# touch_glove.net
KiCad netlist of a schematic drawn in EAGLE
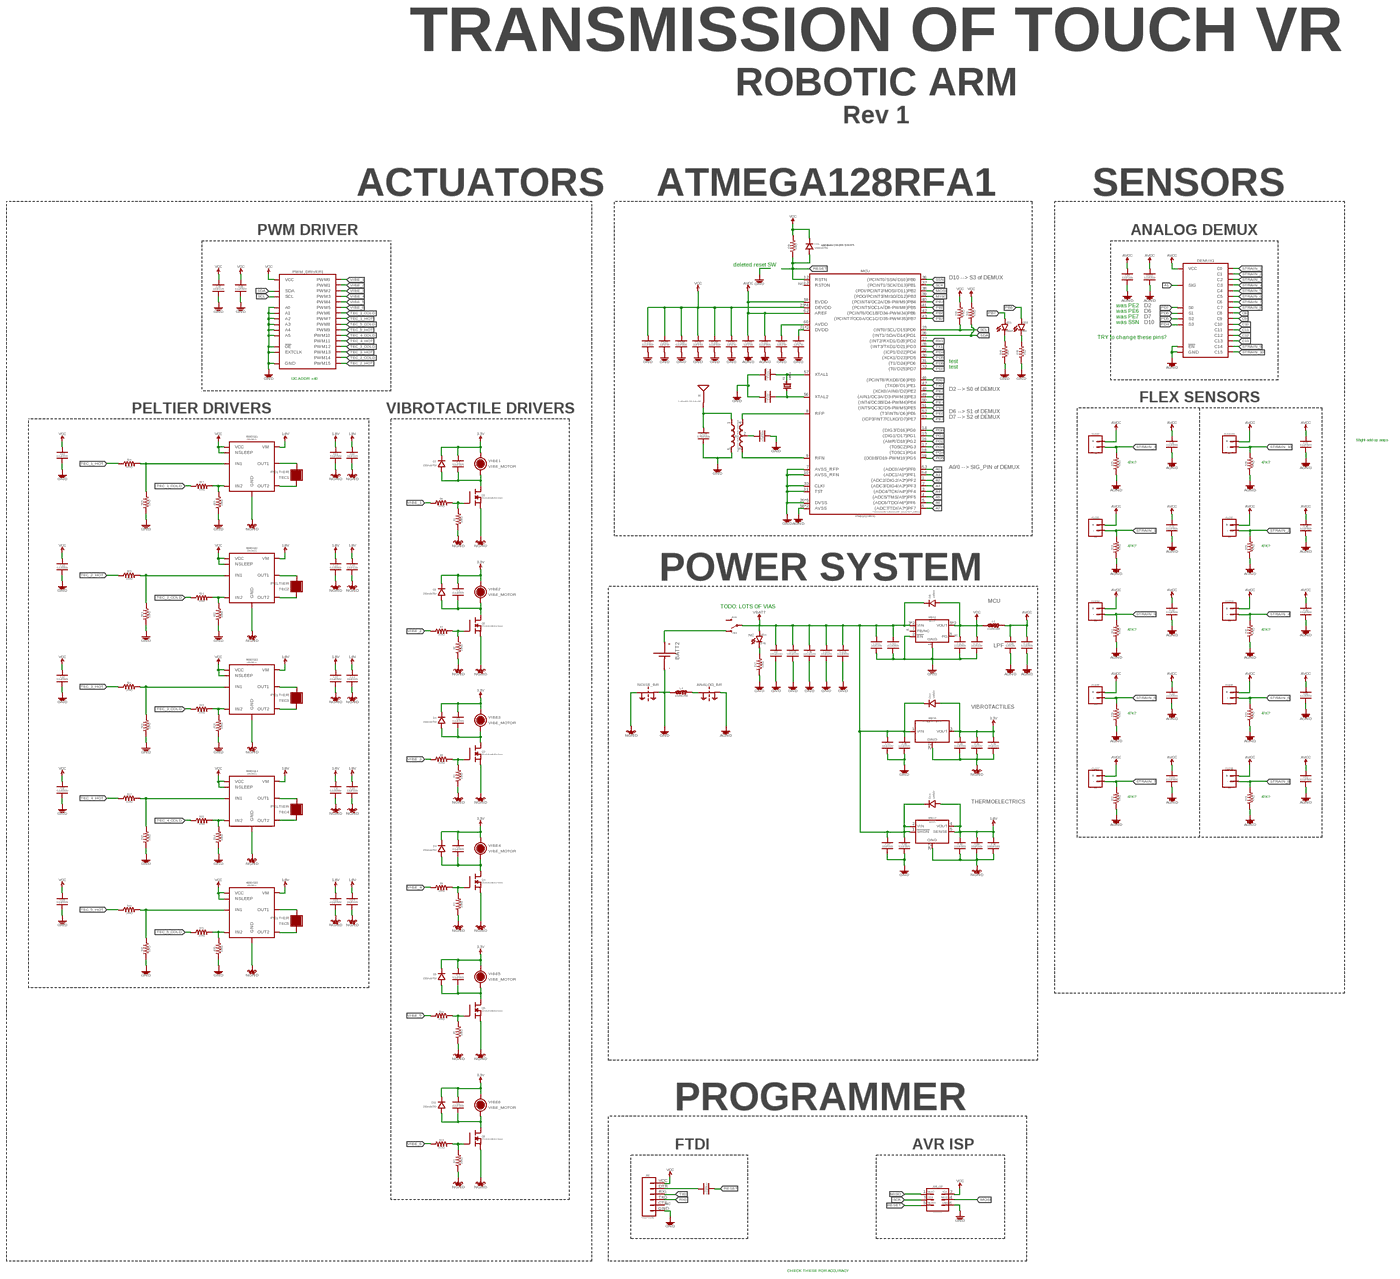
[diagram p0: schematic, sheet 1, overview]
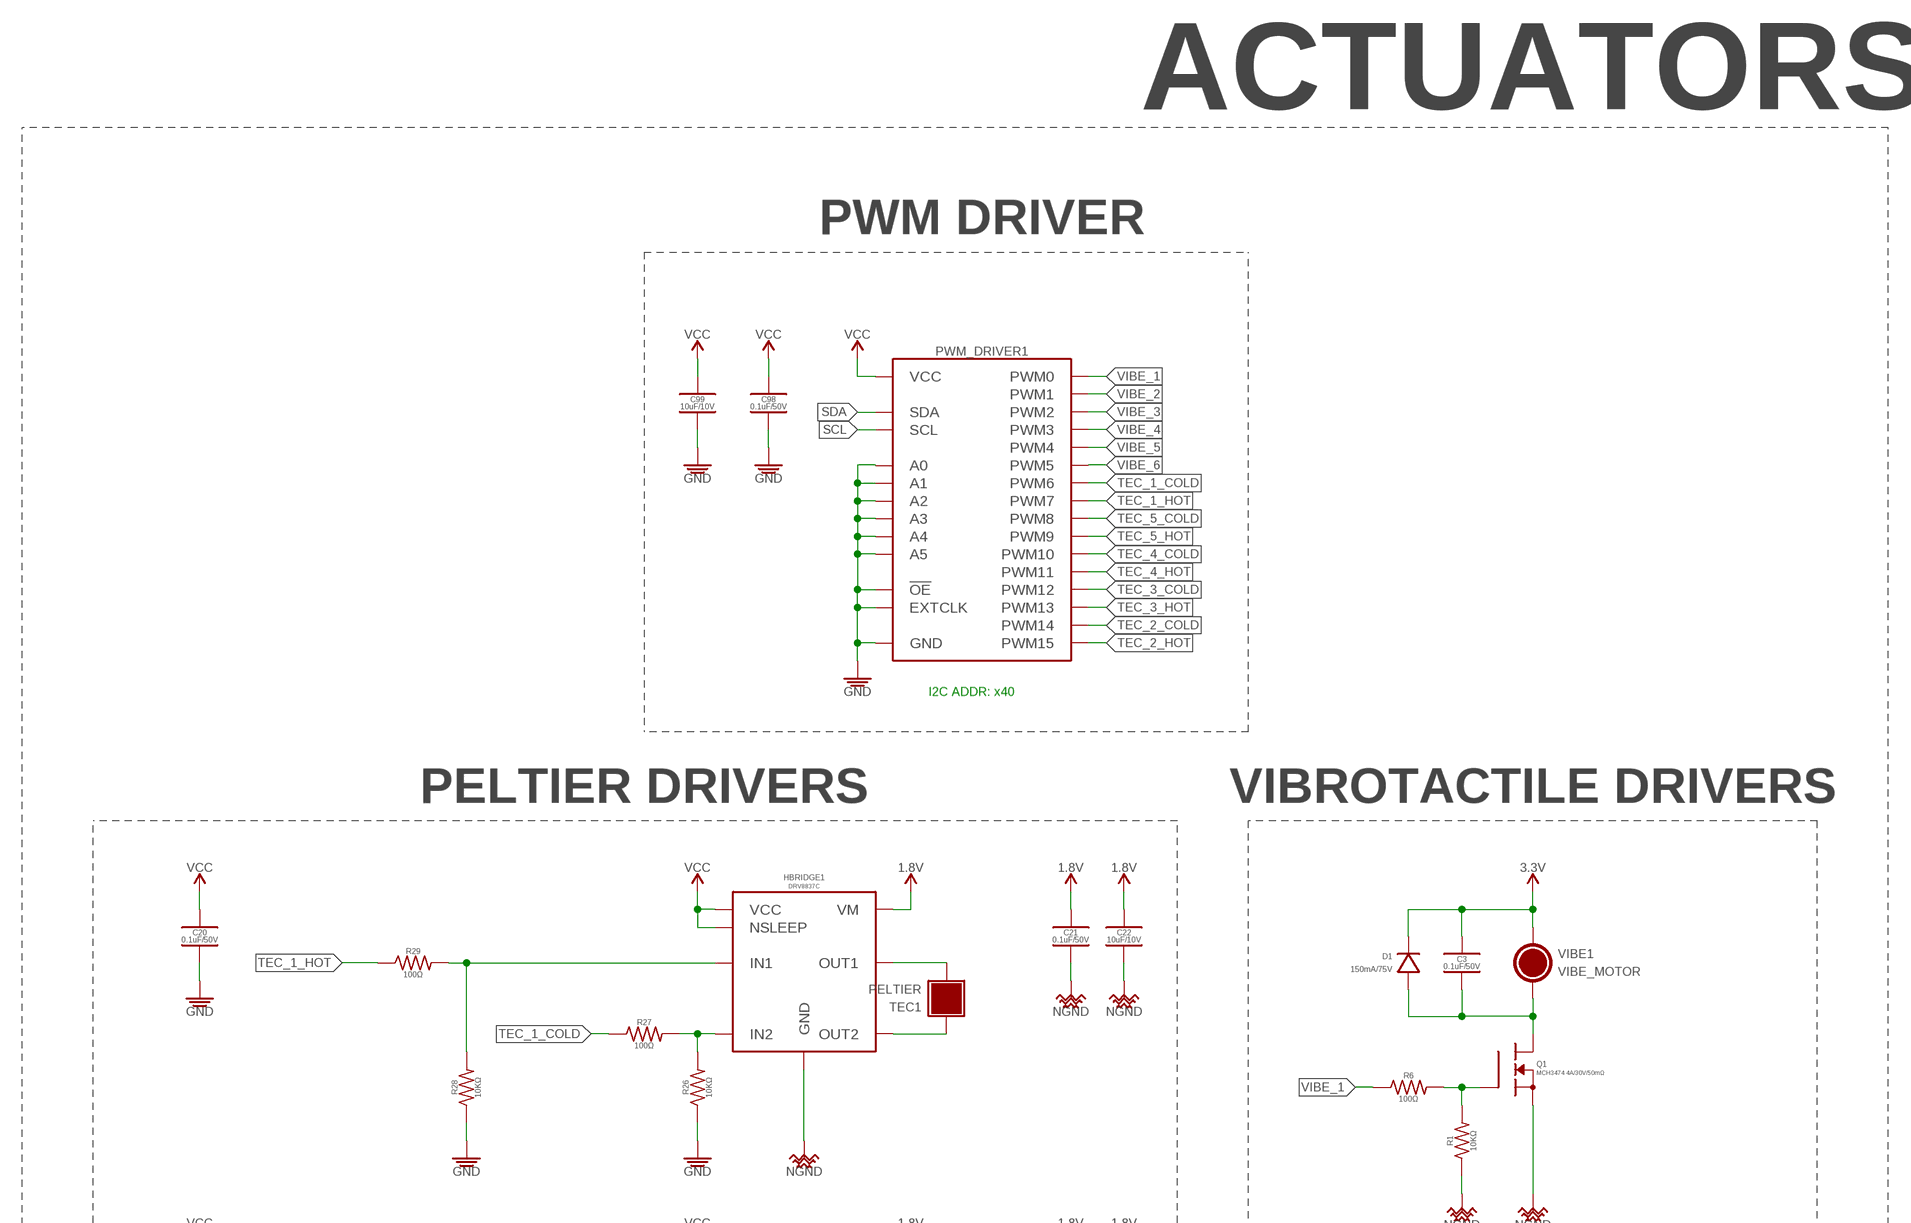
[diagram p1: schematic, sheet 1, part 1 of 4]
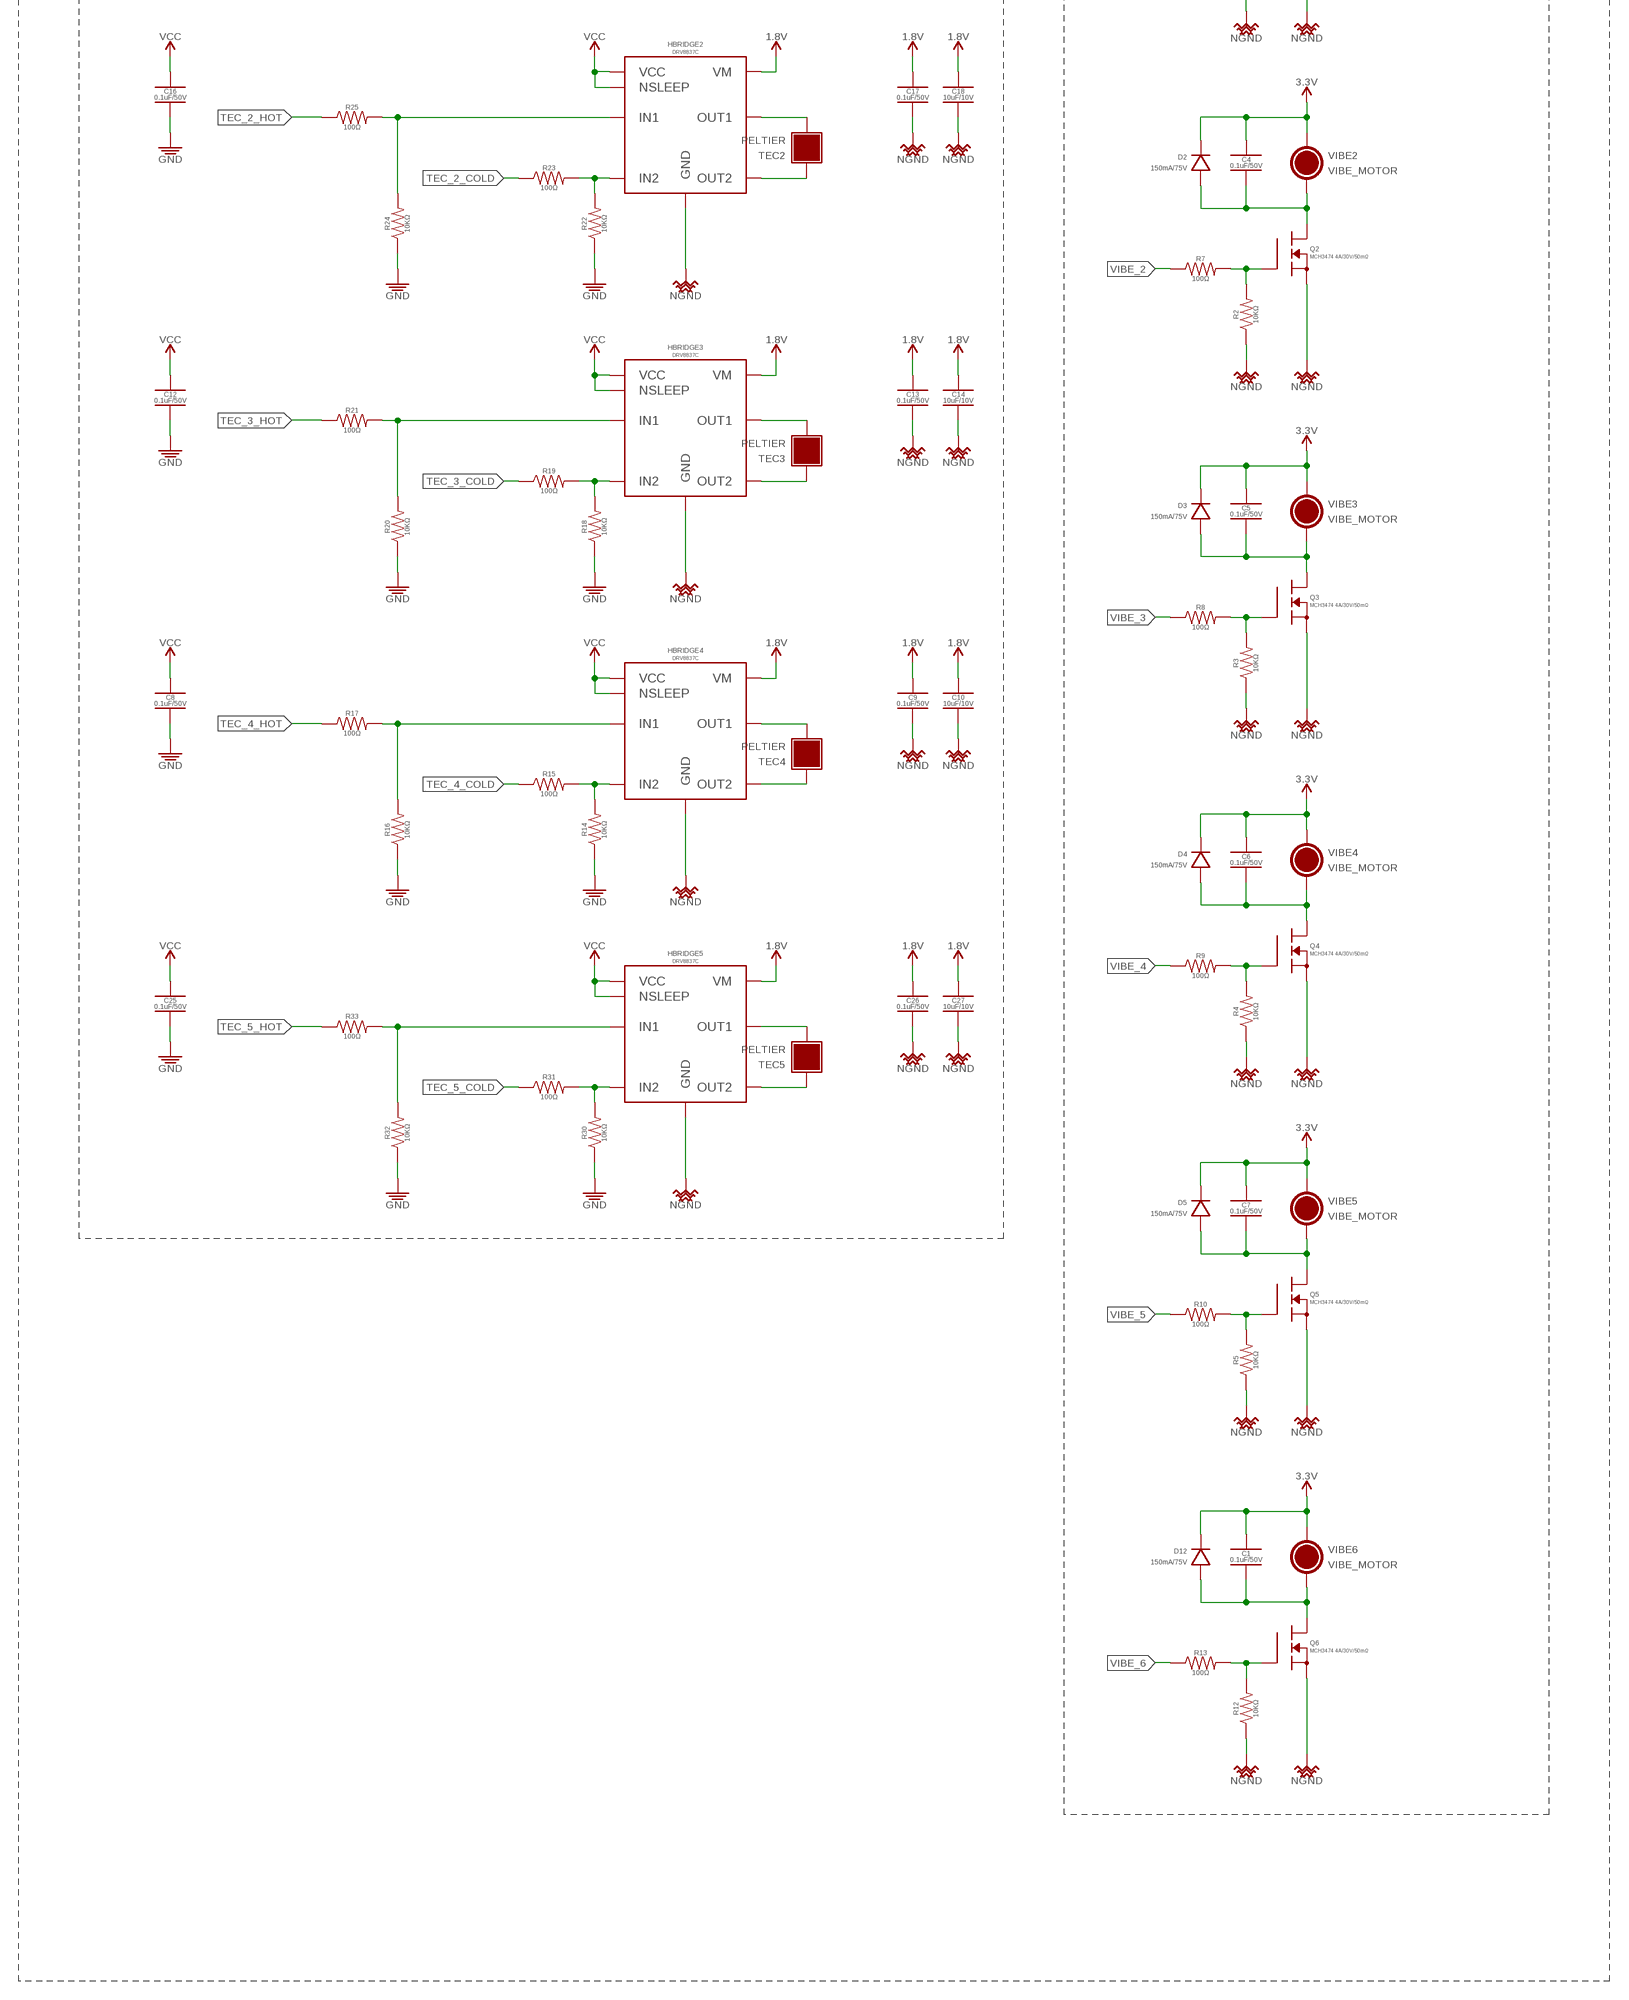
[diagram p2: schematic, sheet 1, part 2 of 4]
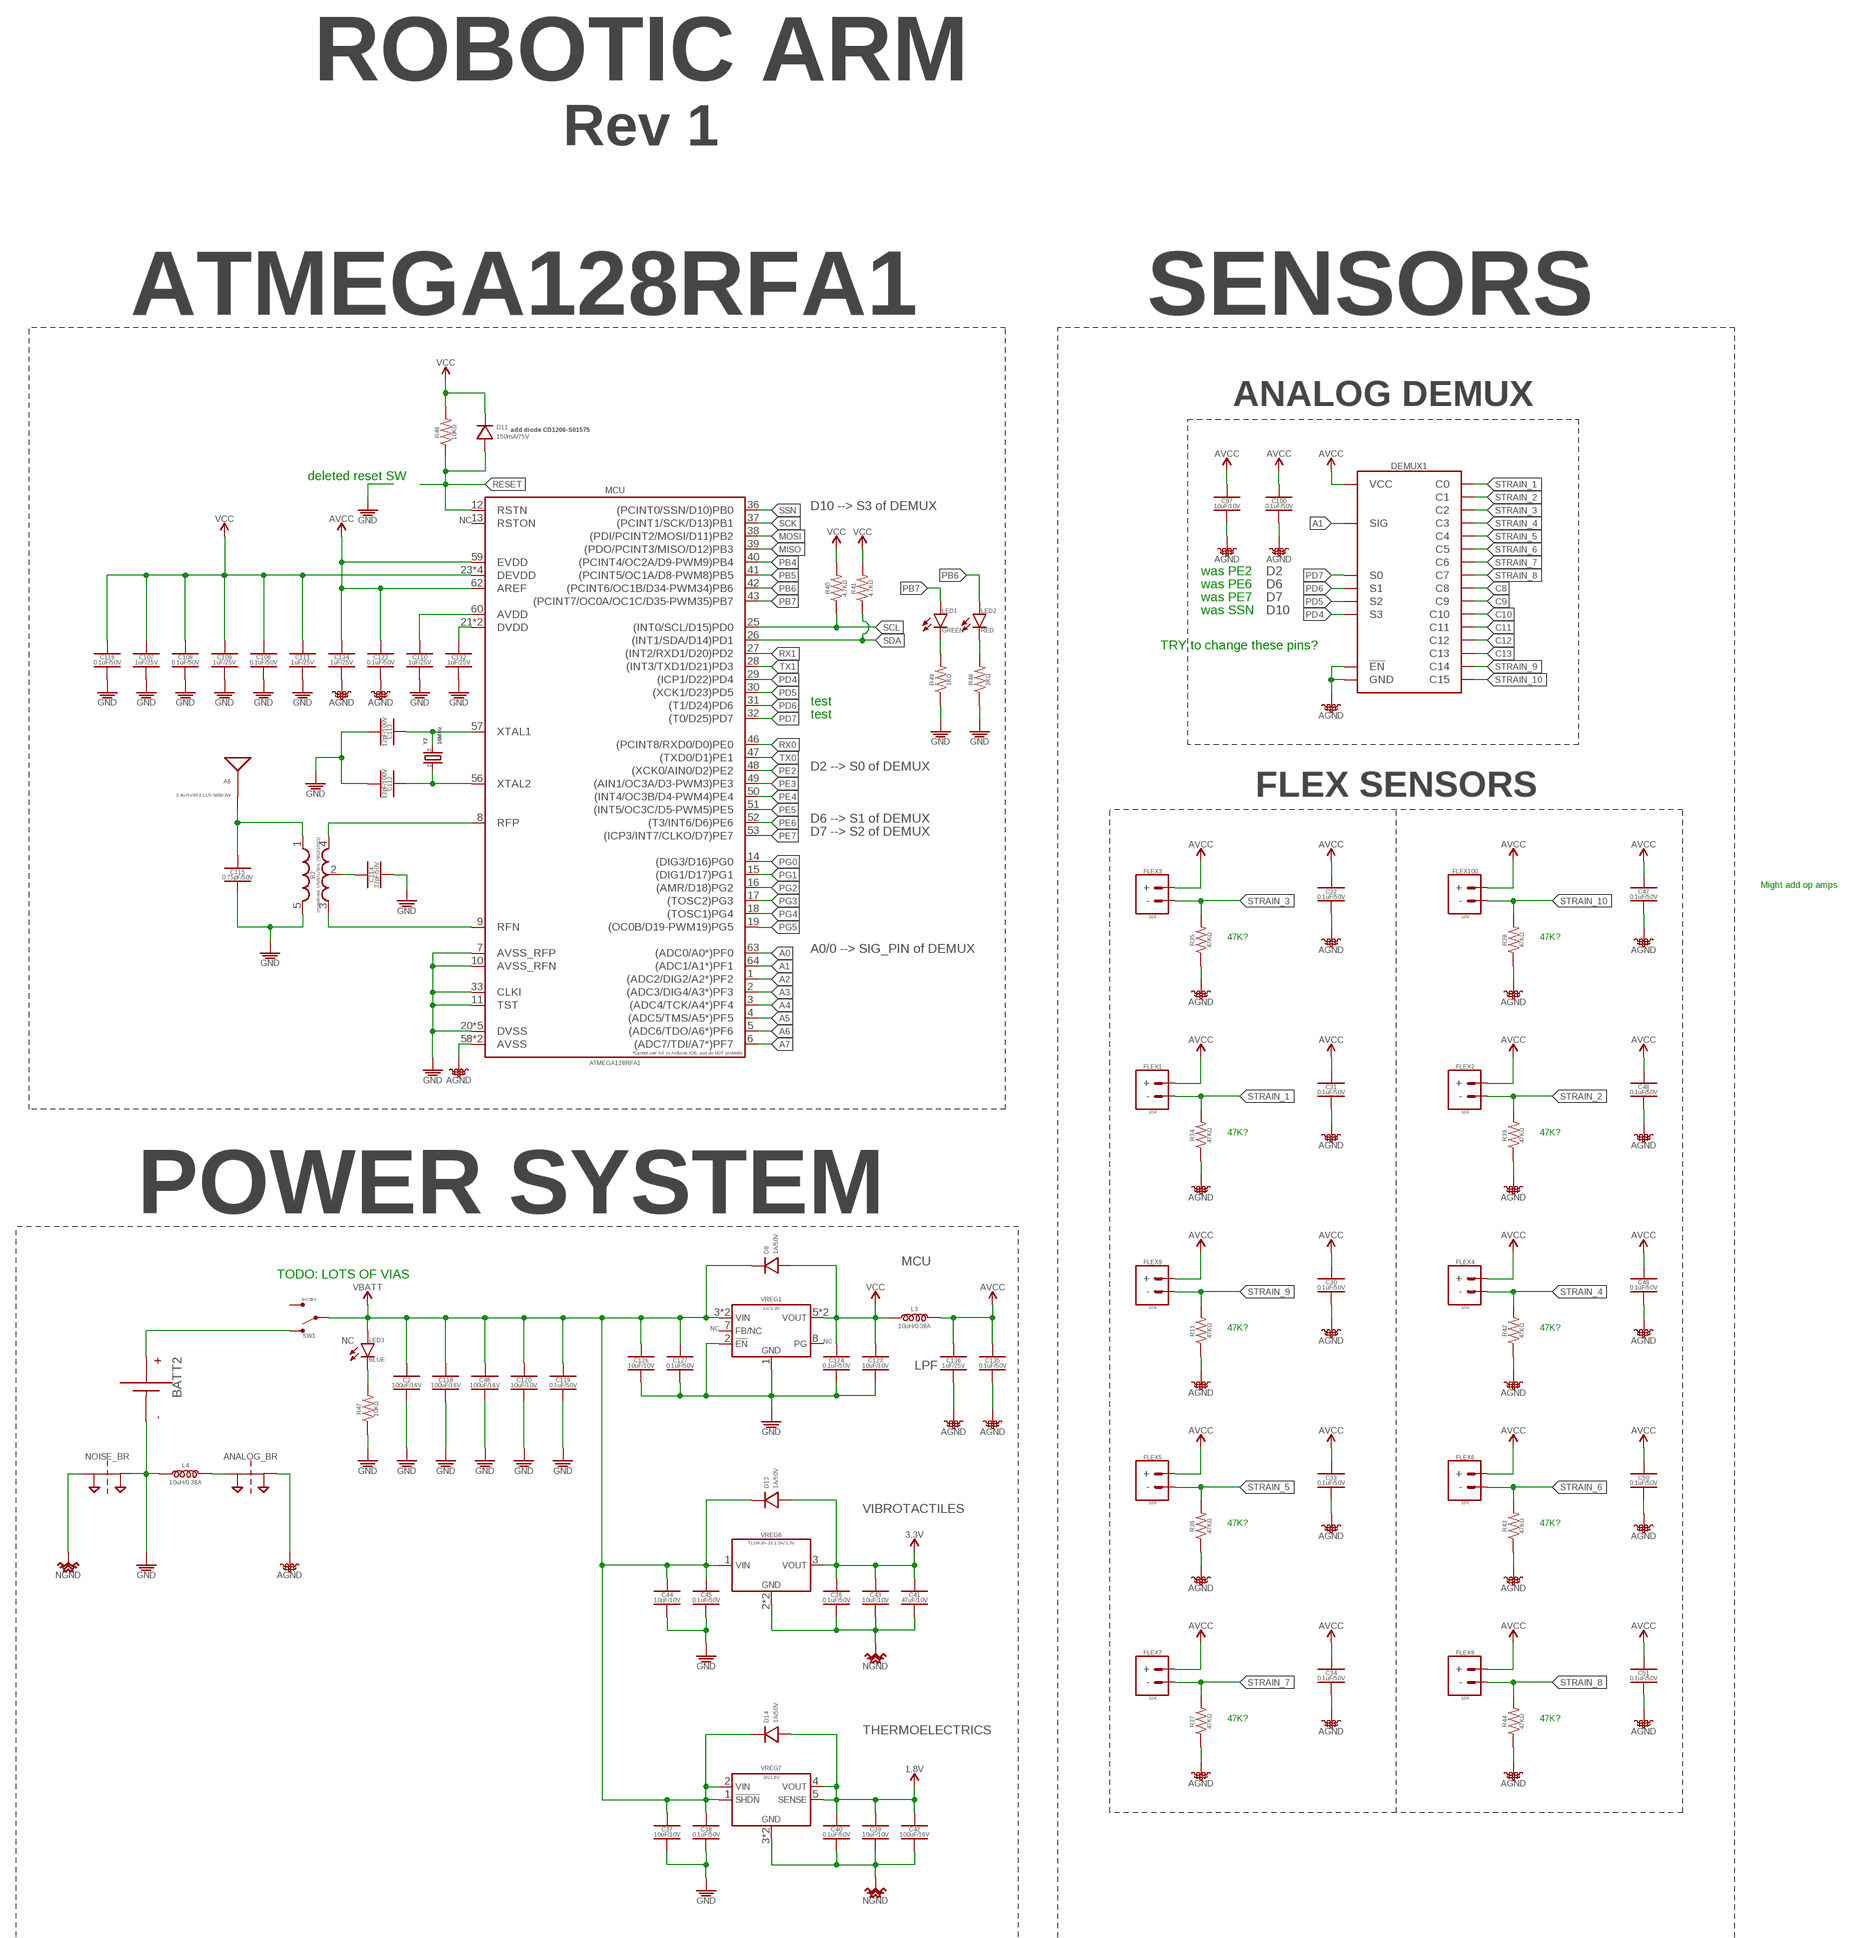
[diagram p3: schematic, sheet 1, part 3 of 4]
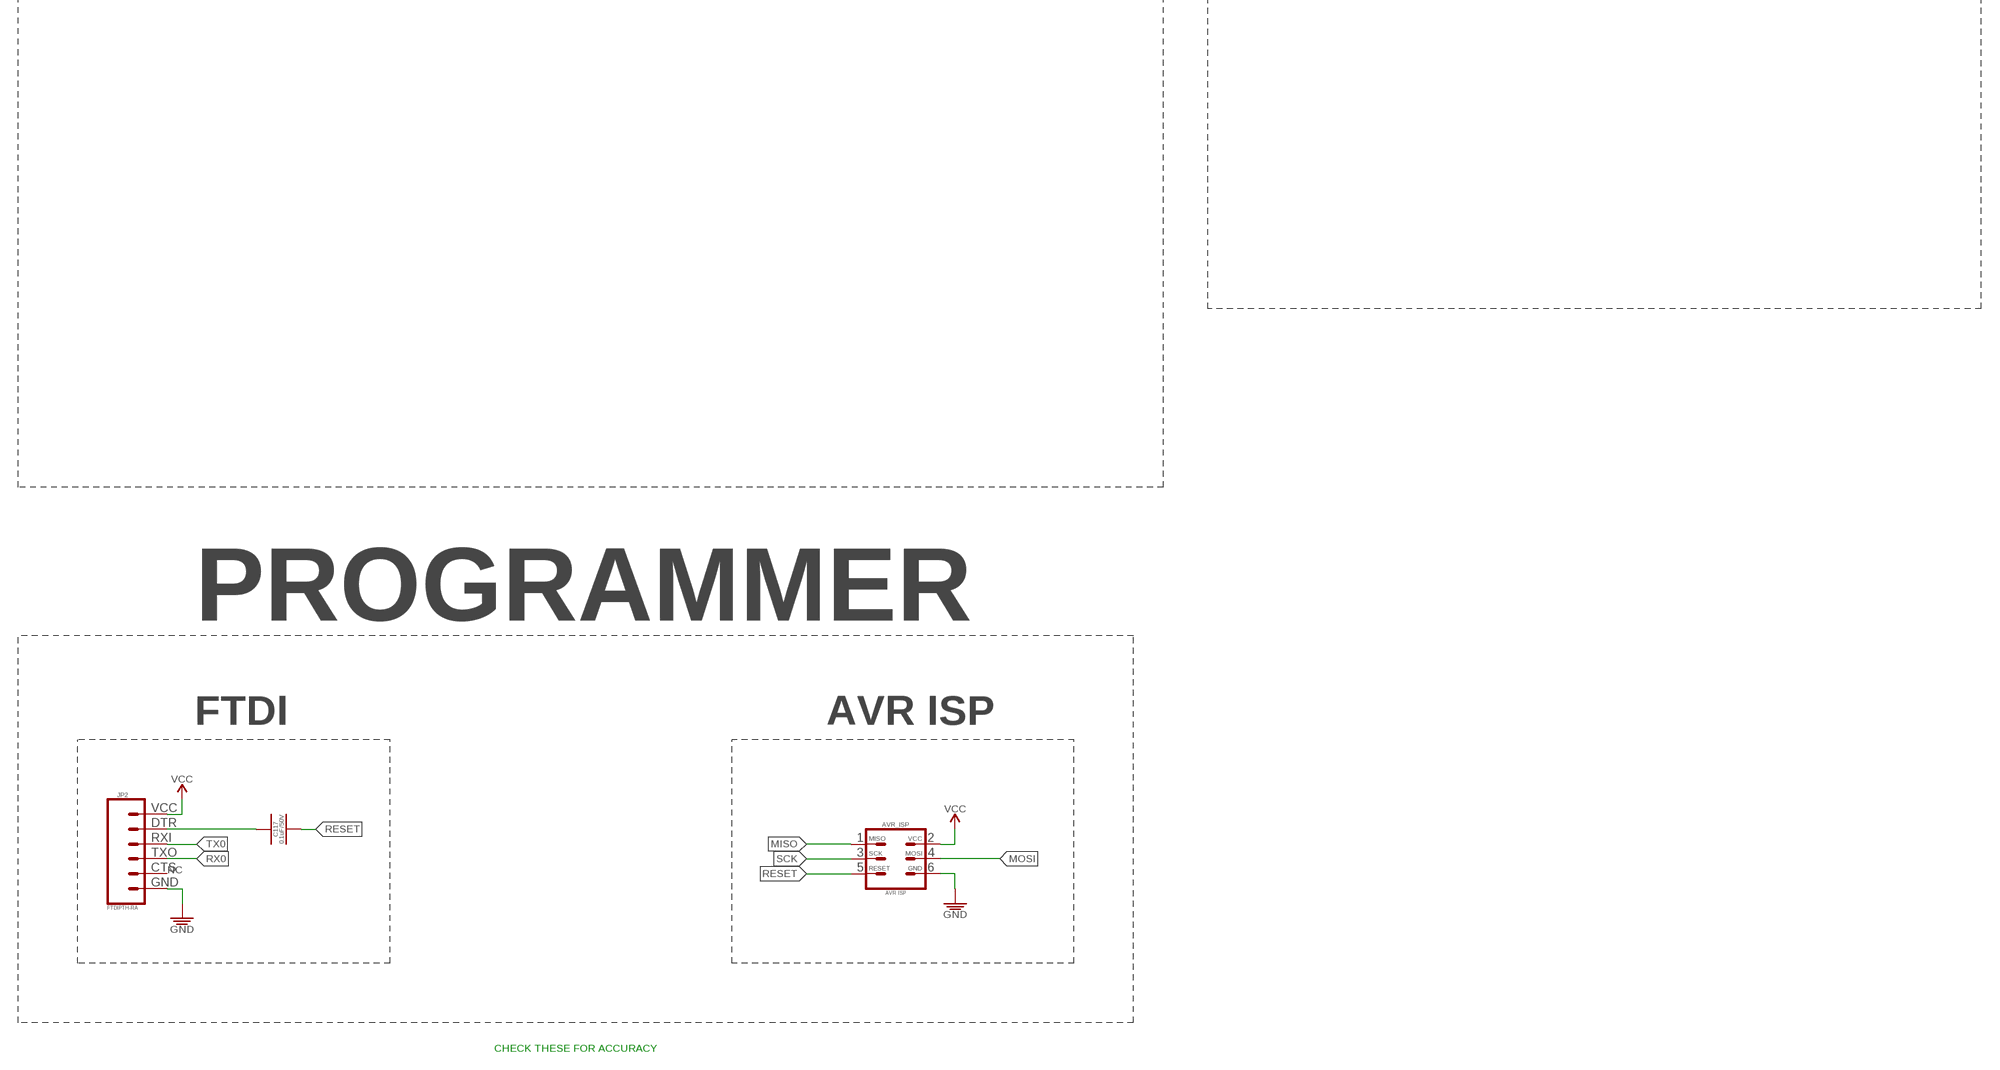
[diagram p4: schematic, sheet 1, part 4 of 4]

(export (version "E")
  (design (tool "Eeschema 10.0.6"))
  (components
    (comp (ref "A6")
      (value "2.4GHz/802.11/0.5dBi/3W")
      (footprint "eagle-import:ANTENNA-CHIP5")
      (fields
        (field (name "MFR") "Linx Technologies Inc.")
        (field (name "MPN") "ANT-2.45-CHP-T")
        (field (name "CREATOR") "Kenmei")
      )
      (libsource (lib "eagle-import") (part "ANTENNA_SMD-CHIP_2.4GHZ-0.5DBI-3W"))
    )
    (comp (ref "ANALOG_BR")
      (value "2PT_GND_TIE")
      (footprint "eagle-import:2PT_GND_TIE")
      (libsource (lib "eagle-import") (part "2PT_GND_TIE"))
    )
    (comp (ref "AVR_ISP")
      (value "AVR ISP")
      (footprint "eagle-import:2X3-NS")
      (fields (field (name "MFR") "Amphenol FCI") (field (name "MPN") "67997-206HLF"))
      (libsource (lib "eagle-import") (part "AVR_SPI_PRG_6NS"))
    )
    (comp (ref "B2")
      (value "Impedence UNBAL/BAL (50Ω/100Ω)")
      (footprint "eagle-import:0805_BALUN")
      (fields
        (field (name "MFR") "Wurth Electronics Inc")
        (field (name "MPN") "748421245")
        (field (name "CREATOR") "Kenmei")
      )
      (libsource (lib "eagle-import") (part "BALUN_SMD-0805_UNBAL/BAL-50/100"))
    )
    (comp (ref "BATT2")
      (value "BATTERYPTH_HOLES")
      (footprint "eagle-import:DUAL_PTH_PADS")
      (libsource (lib "eagle-import") (part "BATTERYPTH_HOLES"))
    )
    (comp (ref "C1")
      (value "0.1uF/50V")
      (footprint "eagle-import:_CER_SMD_0402")
      (fields
        (field (name "MFR") "Murata Electronics North America")
        (field (name "MPN") "GRM155R61H104KE19D")
        (field (name "CREATOR") "MrSwirlyEyes")
      )
      (libsource (lib "eagle-import") (part "0.1UF_SMD-0402_50V-10%"))
    )
    (comp (ref "C2")
      (value "100uF/16V")
      (footprint "eagle-import:_CER_SMD-1210")
      (fields
        (field (name "MFR") "Taiyo Yuden")
        (field (name "MPN") "EMK325ABJ107MM-T")
        (field (name "CREATOR") "MrSwirlyEyes")
      )
      (libsource (lib "eagle-import") (part "100UF_CER_SMD-1210_16V-20%"))
    )
    (comp (ref "C3")
      (value "0.1uF/50V")
      (footprint "eagle-import:_CER_SMD_0402")
      (fields
        (field (name "MFR") "Murata Electronics North America")
        (field (name "MPN") "GRM155R61H104KE19D")
        (field (name "CREATOR") "MrSwirlyEyes")
      )
      (libsource (lib "eagle-import") (part "0.1UF_SMD-0402_50V-10%"))
    )
    (comp (ref "C4")
      (value "0.1uF/50V")
      (footprint "eagle-import:_CER_SMD_0402")
      (fields
        (field (name "MFR") "Murata Electronics North America")
        (field (name "MPN") "GRM155R61H104KE19D")
        (field (name "CREATOR") "MrSwirlyEyes")
      )
      (libsource (lib "eagle-import") (part "0.1UF_SMD-0402_50V-10%"))
    )
    (comp (ref "C5")
      (value "0.1uF/50V")
      (footprint "eagle-import:_CER_SMD_0402")
      (fields
        (field (name "MFR") "Murata Electronics North America")
        (field (name "MPN") "GRM155R61H104KE19D")
        (field (name "CREATOR") "MrSwirlyEyes")
      )
      (libsource (lib "eagle-import") (part "0.1UF_SMD-0402_50V-10%"))
    )
    (comp (ref "C6")
      (value "0.1uF/50V")
      (footprint "eagle-import:_CER_SMD_0402")
      (fields
        (field (name "MFR") "Murata Electronics North America")
        (field (name "MPN") "GRM155R61H104KE19D")
        (field (name "CREATOR") "MrSwirlyEyes")
      )
      (libsource (lib "eagle-import") (part "0.1UF_SMD-0402_50V-10%"))
    )
    (comp (ref "C7")
      (value "0.1uF/50V")
      (footprint "eagle-import:_CER_SMD_0402")
      (fields
        (field (name "MFR") "Murata Electronics North America")
        (field (name "MPN") "GRM155R61H104KE19D")
        (field (name "CREATOR") "MrSwirlyEyes")
      )
      (libsource (lib "eagle-import") (part "0.1UF_SMD-0402_50V-10%"))
    )
    (comp (ref "C8")
      (value "0.1uF/50V")
      (footprint "eagle-import:_CER_SMD_0402")
      (fields
        (field (name "MFR") "Murata Electronics North America")
        (field (name "MPN") "GRM155R61H104KE19D")
        (field (name "CREATOR") "MrSwirlyEyes")
      )
      (libsource (lib "eagle-import") (part "0.1UF_SMD-0402_50V-10%"))
    )
    (comp (ref "C9")
      (value "0.1uF/50V")
      (footprint "eagle-import:_CER_SMD_0402")
      (fields
        (field (name "MFR") "Murata Electronics North America")
        (field (name "MPN") "GRM155R61H104KE19D")
        (field (name "CREATOR") "MrSwirlyEyes")
      )
      (libsource (lib "eagle-import") (part "0.1UF_SMD-0402_50V-10%"))
    )
    (comp (ref "C10")
      (value "10uF/10V")
      (footprint "eagle-import:_CER_SMD_0402")
      (fields
        (field (name "MFR") "Samsung Electro-Mechanics")
        (field (name "MPN") "CL05A106MP5NUNC")
        (field (name "CREATOR") "MrSwirlyEyes")
      )
      (libsource (lib "eagle-import") (part "10UF_CER_SMD-0402_10V-20%"))
    )
    (comp (ref "C12")
      (value "0.1uF/50V")
      (footprint "eagle-import:_CER_SMD_0402")
      (fields
        (field (name "MFR") "Murata Electronics North America")
        (field (name "MPN") "GRM155R61H104KE19D")
        (field (name "CREATOR") "MrSwirlyEyes")
      )
      (libsource (lib "eagle-import") (part "0.1UF_SMD-0402_50V-10%"))
    )
    (comp (ref "C13")
      (value "0.1uF/50V")
      (footprint "eagle-import:_CER_SMD_0402")
      (fields
        (field (name "MFR") "Murata Electronics North America")
        (field (name "MPN") "GRM155R61H104KE19D")
        (field (name "CREATOR") "MrSwirlyEyes")
      )
      (libsource (lib "eagle-import") (part "0.1UF_SMD-0402_50V-10%"))
    )
    (comp (ref "C14")
      (value "10uF/10V")
      (footprint "eagle-import:_CER_SMD_0402")
      (fields
        (field (name "MFR") "Samsung Electro-Mechanics")
        (field (name "MPN") "CL05A106MP5NUNC")
        (field (name "CREATOR") "MrSwirlyEyes")
      )
      (libsource (lib "eagle-import") (part "10UF_CER_SMD-0402_10V-20%"))
    )
    (comp (ref "C16")
      (value "0.1uF/50V")
      (footprint "eagle-import:_CER_SMD_0402")
      (fields
        (field (name "MFR") "Murata Electronics North America")
        (field (name "MPN") "GRM155R61H104KE19D")
        (field (name "CREATOR") "MrSwirlyEyes")
      )
      (libsource (lib "eagle-import") (part "0.1UF_SMD-0402_50V-10%"))
    )
    (comp (ref "C17")
      (value "0.1uF/50V")
      (footprint "eagle-import:_CER_SMD_0402")
      (fields
        (field (name "MFR") "Murata Electronics North America")
        (field (name "MPN") "GRM155R61H104KE19D")
        (field (name "CREATOR") "MrSwirlyEyes")
      )
      (libsource (lib "eagle-import") (part "0.1UF_SMD-0402_50V-10%"))
    )
    (comp (ref "C18")
      (value "10uF/10V")
      (footprint "eagle-import:_CER_SMD_0402")
      (fields
        (field (name "MFR") "Samsung Electro-Mechanics")
        (field (name "MPN") "CL05A106MP5NUNC")
        (field (name "CREATOR") "MrSwirlyEyes")
      )
      (libsource (lib "eagle-import") (part "10UF_CER_SMD-0402_10V-20%"))
    )
    (comp (ref "C20")
      (value "0.1uF/50V")
      (footprint "eagle-import:_CER_SMD_0402")
      (fields
        (field (name "MFR") "Murata Electronics North America")
        (field (name "MPN") "GRM155R61H104KE19D")
        (field (name "CREATOR") "MrSwirlyEyes")
      )
      (libsource (lib "eagle-import") (part "0.1UF_SMD-0402_50V-10%"))
    )
    (comp (ref "C21")
      (value "0.1uF/50V")
      (footprint "eagle-import:_CER_SMD_0402")
      (fields
        (field (name "MFR") "Murata Electronics North America")
        (field (name "MPN") "GRM155R61H104KE19D")
        (field (name "CREATOR") "MrSwirlyEyes")
      )
      (libsource (lib "eagle-import") (part "0.1UF_SMD-0402_50V-10%"))
    )
    (comp (ref "C22")
      (value "10uF/10V")
      (footprint "eagle-import:_CER_SMD_0402")
      (fields
        (field (name "MFR") "Samsung Electro-Mechanics")
        (field (name "MPN") "CL05A106MP5NUNC")
        (field (name "CREATOR") "MrSwirlyEyes")
      )
      (libsource (lib "eagle-import") (part "10UF_CER_SMD-0402_10V-20%"))
    )
    (comp (ref "C25")
      (value "0.1uF/50V")
      (footprint "eagle-import:_CER_SMD_0402")
      (fields
        (field (name "MFR") "Murata Electronics North America")
        (field (name "MPN") "GRM155R61H104KE19D")
        (field (name "CREATOR") "MrSwirlyEyes")
      )
      (libsource (lib "eagle-import") (part "0.1UF_SMD-0402_50V-10%"))
    )
    (comp (ref "C26")
      (value "0.1uF/50V")
      (footprint "eagle-import:_CER_SMD_0402")
      (fields
        (field (name "MFR") "Murata Electronics North America")
        (field (name "MPN") "GRM155R61H104KE19D")
        (field (name "CREATOR") "MrSwirlyEyes")
      )
      (libsource (lib "eagle-import") (part "0.1UF_SMD-0402_50V-10%"))
    )
    (comp (ref "C27")
      (value "10uF/10V")
      (footprint "eagle-import:_CER_SMD_0402")
      (fields
        (field (name "MFR") "Samsung Electro-Mechanics")
        (field (name "MPN") "CL05A106MP5NUNC")
        (field (name "CREATOR") "MrSwirlyEyes")
      )
      (libsource (lib "eagle-import") (part "10UF_CER_SMD-0402_10V-20%"))
    )
    (comp (ref "C30")
      (value "0.1uF/50V")
      (footprint "eagle-import:_CER_SMD_0402")
      (fields
        (field (name "MFR") "Murata Electronics North America")
        (field (name "MPN") "GRM155R61H104KE19D")
        (field (name "CREATOR") "MrSwirlyEyes")
      )
      (libsource (lib "eagle-import") (part "0.1UF_SMD-0402_50V-10%"))
    )
    (comp (ref "C31")
      (value "0.1uF/50V")
      (footprint "eagle-import:_CER_SMD_0402")
      (fields
        (field (name "MFR") "Murata Electronics North America")
        (field (name "MPN") "GRM155R61H104KE19D")
        (field (name "CREATOR") "MrSwirlyEyes")
      )
      (libsource (lib "eagle-import") (part "0.1UF_SMD-0402_50V-10%"))
    )
    (comp (ref "C32")
      (value "0.1uF/50V")
      (footprint "eagle-import:_CER_SMD_0402")
      (fields
        (field (name "MFR") "Murata Electronics North America")
        (field (name "MPN") "GRM155R61H104KE19D")
        (field (name "CREATOR") "MrSwirlyEyes")
      )
      (libsource (lib "eagle-import") (part "0.1UF_SMD-0402_50V-10%"))
    )
    (comp (ref "C33")
      (value "0.1uF/50V")
      (footprint "eagle-import:_CER_SMD_0402")
      (fields
        (field (name "MFR") "Murata Electronics North America")
        (field (name "MPN") "GRM155R61H104KE19D")
        (field (name "CREATOR") "MrSwirlyEyes")
      )
      (libsource (lib "eagle-import") (part "0.1UF_SMD-0402_50V-10%"))
    )
    (comp (ref "C34")
      (value "0.1uF/50V")
      (footprint "eagle-import:_CER_SMD_0402")
      (fields
        (field (name "MFR") "Murata Electronics North America")
        (field (name "MPN") "GRM155R61H104KE19D")
        (field (name "CREATOR") "MrSwirlyEyes")
      )
      (libsource (lib "eagle-import") (part "0.1UF_SMD-0402_50V-10%"))
    )
    (comp (ref "C36")
      (value "0.1uF/50V")
      (footprint "eagle-import:_CER_SMD_0402")
      (fields
        (field (name "MFR") "Murata Electronics North America")
        (field (name "MPN") "GRM155R61H104KE19D")
        (field (name "CREATOR") "MrSwirlyEyes")
      )
      (libsource (lib "eagle-import") (part "0.1UF_SMD-0402_50V-10%"))
    )
    (comp (ref "C37")
      (value "10uF/10V")
      (footprint "eagle-import:_CER_SMD_0402")
      (fields
        (field (name "MFR") "Samsung Electro-Mechanics")
        (field (name "MPN") "CL05A106MP5NUNC")
        (field (name "CREATOR") "MrSwirlyEyes")
      )
      (libsource (lib "eagle-import") (part "10UF_CER_SMD-0402_10V-20%"))
    )
    (comp (ref "C38")
      (value "0.1uF/50V")
      (footprint "eagle-import:_CER_SMD_0402")
      (fields
        (field (name "MFR") "Murata Electronics North America")
        (field (name "MPN") "GRM155R61H104KE19D")
        (field (name "CREATOR") "MrSwirlyEyes")
      )
      (libsource (lib "eagle-import") (part "0.1UF_SMD-0402_50V-10%"))
    )
    (comp (ref "C39")
      (value "10uF/10V")
      (footprint "eagle-import:_CER_SMD_0402")
      (fields
        (field (name "MFR") "Samsung Electro-Mechanics")
        (field (name "MPN") "CL05A106MP5NUNC")
        (field (name "CREATOR") "MrSwirlyEyes")
      )
      (libsource (lib "eagle-import") (part "10UF_CER_SMD-0402_10V-20%"))
    )
    (comp (ref "C40")
      (value "0.1uF/50V")
      (footprint "eagle-import:_CER_SMD_0402")
      (fields
        (field (name "MFR") "Murata Electronics North America")
        (field (name "MPN") "GRM155R61H104KE19D")
        (field (name "CREATOR") "MrSwirlyEyes")
      )
      (libsource (lib "eagle-import") (part "0.1UF_SMD-0402_50V-10%"))
    )
    (comp (ref "C41")
      (value "47uF/10V")
      (footprint "eagle-import:_CER_SMD-805")
      (fields
        (field (name "MFR") "Murata Electronics North America")
        (field (name "MPN") "GRM21BR61A476ME15L")
        (field (name "CREATOR") "MrSwirlyEyes")
      )
      (libsource (lib "eagle-import") (part "47UF_CER_SMD-0805_10V-20%"))
    )
    (comp (ref "C42")
      (value "100uF/16V")
      (footprint "eagle-import:_CER_SMD-1210")
      (fields
        (field (name "MFR") "Taiyo Yuden")
        (field (name "MPN") "EMK325ABJ107MM-T")
        (field (name "CREATOR") "MrSwirlyEyes")
      )
      (libsource (lib "eagle-import") (part "100UF_CER_SMD-1210_16V-20%"))
    )
    (comp (ref "C43")
      (value "10uF/10V")
      (footprint "eagle-import:_CER_SMD_0402")
      (fields
        (field (name "MFR") "Samsung Electro-Mechanics")
        (field (name "MPN") "CL05A106MP5NUNC")
        (field (name "CREATOR") "MrSwirlyEyes")
      )
      (libsource (lib "eagle-import") (part "10UF_CER_SMD-0402_10V-20%"))
    )
    (comp (ref "C44")
      (value "10uF/10V")
      (footprint "eagle-import:_CER_SMD_0402")
      (fields
        (field (name "MFR") "Samsung Electro-Mechanics")
        (field (name "MPN") "CL05A106MP5NUNC")
        (field (name "CREATOR") "MrSwirlyEyes")
      )
      (libsource (lib "eagle-import") (part "10UF_CER_SMD-0402_10V-20%"))
    )
    (comp (ref "C45")
      (value "0.1uF/50V")
      (footprint "eagle-import:_CER_SMD_0402")
      (fields
        (field (name "MFR") "Murata Electronics North America")
        (field (name "MPN") "GRM155R61H104KE19D")
        (field (name "CREATOR") "MrSwirlyEyes")
      )
      (libsource (lib "eagle-import") (part "0.1UF_SMD-0402_50V-10%"))
    )
    (comp (ref "C46")
      (value "100uF/16V")
      (footprint "eagle-import:_CER_SMD-1210")
      (fields
        (field (name "MFR") "Taiyo Yuden")
        (field (name "MPN") "EMK325ABJ107MM-T")
        (field (name "CREATOR") "MrSwirlyEyes")
      )
      (libsource (lib "eagle-import") (part "100UF_CER_SMD-1210_16V-20%"))
    )
    (comp (ref "C47")
      (value "0.1uF/50V")
      (footprint "eagle-import:_CER_SMD_0402")
      (fields
        (field (name "MFR") "Murata Electronics North America")
        (field (name "MPN") "GRM155R61H104KE19D")
        (field (name "CREATOR") "MrSwirlyEyes")
      )
      (libsource (lib "eagle-import") (part "0.1UF_SMD-0402_50V-10%"))
    )
    (comp (ref "C48")
      (value "0.1uF/50V")
      (footprint "eagle-import:_CER_SMD_0402")
      (fields
        (field (name "MFR") "Murata Electronics North America")
        (field (name "MPN") "GRM155R61H104KE19D")
        (field (name "CREATOR") "MrSwirlyEyes")
      )
      (libsource (lib "eagle-import") (part "0.1UF_SMD-0402_50V-10%"))
    )
    (comp (ref "C49")
      (value "0.1uF/50V")
      (footprint "eagle-import:_CER_SMD_0402")
      (fields
        (field (name "MFR") "Murata Electronics North America")
        (field (name "MPN") "GRM155R61H104KE19D")
        (field (name "CREATOR") "MrSwirlyEyes")
      )
      (libsource (lib "eagle-import") (part "0.1UF_SMD-0402_50V-10%"))
    )
    (comp (ref "C50")
      (value "0.1uF/50V")
      (footprint "eagle-import:_CER_SMD_0402")
      (fields
        (field (name "MFR") "Murata Electronics North America")
        (field (name "MPN") "GRM155R61H104KE19D")
        (field (name "CREATOR") "MrSwirlyEyes")
      )
      (libsource (lib "eagle-import") (part "0.1UF_SMD-0402_50V-10%"))
    )
    (comp (ref "C51")
      (value "0.1uF/50V")
      (footprint "eagle-import:_CER_SMD_0402")
      (fields
        (field (name "MFR") "Murata Electronics North America")
        (field (name "MPN") "GRM155R61H104KE19D")
        (field (name "CREATOR") "MrSwirlyEyes")
      )
      (libsource (lib "eagle-import") (part "0.1UF_SMD-0402_50V-10%"))
    )
    (comp (ref "C97")
      (value "10uF/10V")
      (footprint "eagle-import:_CER_SMD_0402")
      (fields
        (field (name "MFR") "Samsung Electro-Mechanics")
        (field (name "MPN") "CL05A106MP5NUNC")
        (field (name "CREATOR") "MrSwirlyEyes")
      )
      (libsource (lib "eagle-import") (part "10UF_CER_SMD-0402_10V-20%"))
    )
    (comp (ref "C98")
      (value "0.1uF/50V")
      (footprint "eagle-import:_CER_SMD_0402")
      (fields
        (field (name "MFR") "Murata Electronics North America")
        (field (name "MPN") "GRM155R61H104KE19D")
        (field (name "CREATOR") "MrSwirlyEyes")
      )
      (libsource (lib "eagle-import") (part "0.1UF_SMD-0402_50V-10%"))
    )
    (comp (ref "C99")
      (value "10uF/10V")
      (footprint "eagle-import:_CER_SMD_0402")
      (fields
        (field (name "MFR") "Samsung Electro-Mechanics")
        (field (name "MPN") "CL05A106MP5NUNC")
        (field (name "CREATOR") "MrSwirlyEyes")
      )
      (libsource (lib "eagle-import") (part "10UF_CER_SMD-0402_10V-20%"))
    )
    (comp (ref "C100")
      (value "0.1uF/50V")
      (footprint "eagle-import:_CER_SMD_0402")
      (fields
        (field (name "MFR") "Murata Electronics North America")
        (field (name "MPN") "GRM155R61H104KE19D")
        (field (name "CREATOR") "MrSwirlyEyes")
      )
      (libsource (lib "eagle-import") (part "0.1UF_SMD-0402_50V-10%"))
    )
    (comp (ref "C106")
      (value "0.1uF/50V")
      (footprint "eagle-import:_CER_SMD_0402")
      (fields
        (field (name "MFR") "Murata Electronics North America")
        (field (name "MPN") "GRM155R61H104KE19D")
        (field (name "CREATOR") "MrSwirlyEyes")
      )
      (libsource (lib "eagle-import") (part "0.1UF_SMD-0402_50V-10%"))
    )
    (comp (ref "C107")
      (value "1uF/25V")
      (footprint "eagle-import:_CER_SMD_0402")
      (fields
        (field (name "MFR") "Murata Electronics North America")
        (field (name "MPN") "GRM155C81E105KE11D")
        (field (name "CREATOR") "MrSwirlyEyes")
      )
      (libsource (lib "eagle-import") (part "1UF_CER_SMD-0402_25V-10%"))
    )
    (comp (ref "C108")
      (value "0.1uF/50V")
      (footprint "eagle-import:_CER_SMD_0402")
      (fields
        (field (name "MFR") "Murata Electronics North America")
        (field (name "MPN") "GRM155R61H104KE19D")
        (field (name "CREATOR") "MrSwirlyEyes")
      )
      (libsource (lib "eagle-import") (part "0.1UF_SMD-0402_50V-10%"))
    )
    (comp (ref "C109")
      (value "1uF/25V")
      (footprint "eagle-import:_CER_SMD_0402")
      (fields
        (field (name "MFR") "Murata Electronics North America")
        (field (name "MPN") "GRM155C81E105KE11D")
        (field (name "CREATOR") "MrSwirlyEyes")
      )
      (libsource (lib "eagle-import") (part "1UF_CER_SMD-0402_25V-10%"))
    )
    (comp (ref "C110")
      (value "1uF/25V")
      (footprint "eagle-import:_CER_SMD_0402")
      (fields
        (field (name "MFR") "Murata Electronics North America")
        (field (name "MPN") "GRM155C81E105KE11D")
        (field (name "CREATOR") "MrSwirlyEyes")
      )
      (libsource (lib "eagle-import") (part "1UF_CER_SMD-0402_25V-10%"))
    )
    (comp (ref "C111")
      (value "1uF/25V")
      (footprint "eagle-import:_CER_SMD_0402")
      (fields
        (field (name "MFR") "Murata Electronics North America")
        (field (name "MPN") "GRM155C81E105KE11D")
        (field (name "CREATOR") "MrSwirlyEyes")
      )
      (libsource (lib "eagle-import") (part "1UF_CER_SMD-0402_25V-10%"))
    )
    (comp (ref "C112")
      (value "12pF/100V")
      (footprint "eagle-import:_CER_SMD_0402")
      (fields
        (field (name "MFR") "Murata Electronics North America")
        (field (name "MPN") "GRM1555C2A120JA01D")
        (field (name "CREATOR") "MrSwirlyEyes")
      )
      (libsource (lib "eagle-import") (part "12PF_SMD-0402_100V-5%"))
    )
    (comp (ref "C113")
      (value "12pF/100V")
      (footprint "eagle-import:_CER_SMD_0402")
      (fields
        (field (name "MFR") "Murata Electronics North America")
        (field (name "MPN") "GRM1555C2A120JA01D")
        (field (name "CREATOR") "MrSwirlyEyes")
      )
      (libsource (lib "eagle-import") (part "12PF_SMD-0402_100V-5%"))
    )
    (comp (ref "C114")
      (value "22pF/50V")
      (footprint "eagle-import:_CER_SMD_0402")
      (fields
        (field (name "MFR") "Murata Electronics North America")
        (field (name "MPN") "GRM1555C1H220JA01D")
        (field (name "CREATOR") "MrSwirlyEyes")
      )
      (libsource (lib "eagle-import") (part "22PF_SMD-0402_100V-5%"))
    )
    (comp (ref "C115")
      (value "0.75pF/50V")
      (footprint "eagle-import:_CER_SMD_0402")
      (fields
        (field (name "MFR") "Murata Electronics North America")
        (field (name "MPN") "GRM1555C1HR75CA01D")
        (field (name "CREATOR") "MrSwirlyEyes")
      )
      (libsource (lib "eagle-import") (part "0.75PF_SMD-0402_50V-33%"))
    )
    (comp (ref "C116")
      (value "0.1uF/50V")
      (footprint "eagle-import:_CER_SMD_0402")
      (fields
        (field (name "MFR") "Murata Electronics North America")
        (field (name "MPN") "GRM155R61H104KE19D")
        (field (name "CREATOR") "MrSwirlyEyes")
      )
      (libsource (lib "eagle-import") (part "0.1UF_SMD-0402_50V-10%"))
    )
    (comp (ref "C117")
      (value "0.1uF/50V")
      (footprint "eagle-import:_CER_SMD_0402")
      (fields
        (field (name "MFR") "Murata Electronics North America")
        (field (name "MPN") "GRM155R61H104KE19D")
        (field (name "CREATOR") "MrSwirlyEyes")
      )
      (libsource (lib "eagle-import") (part "0.1UF_SMD-0402_50V-10%"))
    )
    (comp (ref "C118")
      (value "100uF/16V")
      (footprint "eagle-import:_CER_SMD-1210")
      (fields
        (field (name "MFR") "Taiyo Yuden")
        (field (name "MPN") "EMK325ABJ107MM-T")
        (field (name "CREATOR") "MrSwirlyEyes")
      )
      (libsource (lib "eagle-import") (part "100UF_CER_SMD-1210_16V-20%"))
    )
    (comp (ref "C119")
      (value "0.1uF/50V")
      (footprint "eagle-import:_CER_SMD_0402")
      (fields
        (field (name "MFR") "Murata Electronics North America")
        (field (name "MPN") "GRM155R61H104KE19D")
        (field (name "CREATOR") "MrSwirlyEyes")
      )
      (libsource (lib "eagle-import") (part "0.1UF_SMD-0402_50V-10%"))
    )
    (comp (ref "C120")
      (value "10uF/10V")
      (footprint "eagle-import:_CER_SMD_0402")
      (fields
        (field (name "MFR") "Samsung Electro-Mechanics")
        (field (name "MPN") "CL05A106MP5NUNC")
        (field (name "CREATOR") "MrSwirlyEyes")
      )
      (libsource (lib "eagle-import") (part "10UF_CER_SMD-0402_10V-20%"))
    )
    (comp (ref "C122")
      (value "0.1uF/50V")
      (footprint "eagle-import:_CER_SMD_0402")
      (fields
        (field (name "MFR") "Murata Electronics North America")
        (field (name "MPN") "GRM155R61H104KE19D")
        (field (name "CREATOR") "MrSwirlyEyes")
      )
      (libsource (lib "eagle-import") (part "0.1UF_SMD-0402_50V-10%"))
    )
    (comp (ref "C123")
      (value "10uF/10V")
      (footprint "eagle-import:_CER_SMD_0402")
      (fields
        (field (name "MFR") "Samsung Electro-Mechanics")
        (field (name "MPN") "CL05A106MP5NUNC")
        (field (name "CREATOR") "MrSwirlyEyes")
      )
      (libsource (lib "eagle-import") (part "10UF_CER_SMD-0402_10V-20%"))
    )
    (comp (ref "C124")
      (value "0.1uF/50V")
      (footprint "eagle-import:_CER_SMD_0402")
      (fields
        (field (name "MFR") "Murata Electronics North America")
        (field (name "MPN") "GRM155R61H104KE19D")
        (field (name "CREATOR") "MrSwirlyEyes")
      )
      (libsource (lib "eagle-import") (part "0.1UF_SMD-0402_50V-10%"))
    )
    (comp (ref "C126")
      (value "10uF/10V")
      (footprint "eagle-import:_CER_SMD_0402")
      (fields
        (field (name "MFR") "Samsung Electro-Mechanics")
        (field (name "MPN") "CL05A106MP5NUNC")
        (field (name "CREATOR") "MrSwirlyEyes")
      )
      (libsource (lib "eagle-import") (part "10UF_CER_SMD-0402_10V-20%"))
    )
    (comp (ref "C127")
      (value "0.1uF/50V")
      (footprint "eagle-import:_CER_SMD_0402")
      (fields
        (field (name "MFR") "Murata Electronics North America")
        (field (name "MPN") "GRM155R61H104KE19D")
        (field (name "CREATOR") "MrSwirlyEyes")
      )
      (libsource (lib "eagle-import") (part "0.1UF_SMD-0402_50V-10%"))
    )
    (comp (ref "C132")
      (value "1uF/25V")
      (footprint "eagle-import:_CER_SMD_0402")
      (fields
        (field (name "MFR") "Murata Electronics North America")
        (field (name "MPN") "GRM155C81E105KE11D")
        (field (name "CREATOR") "MrSwirlyEyes")
      )
      (libsource (lib "eagle-import") (part "1UF_CER_SMD-0402_25V-10%"))
    )
    (comp (ref "C134")
      (value "1uF/25V")
      (footprint "eagle-import:_CER_SMD_0402")
      (fields
        (field (name "MFR") "Murata Electronics North America")
        (field (name "MPN") "GRM155C81E105KE11D")
        (field (name "CREATOR") "MrSwirlyEyes")
      )
      (libsource (lib "eagle-import") (part "1UF_CER_SMD-0402_25V-10%"))
    )
    (comp (ref "C135")
      (value "0.1uF/50V")
      (footprint "eagle-import:_CER_SMD_0402")
      (fields
        (field (name "MFR") "Murata Electronics North America")
        (field (name "MPN") "GRM155R61H104KE19D")
        (field (name "CREATOR") "MrSwirlyEyes")
      )
      (libsource (lib "eagle-import") (part "0.1UF_SMD-0402_50V-10%"))
    )
    (comp (ref "C136")
      (value "1uF/25V")
      (footprint "eagle-import:_CER_SMD_0402")
      (fields
        (field (name "MFR") "Murata Electronics North America")
        (field (name "MPN") "GRM155C81E105KE11D")
        (field (name "CREATOR") "MrSwirlyEyes")
      )
      (libsource (lib "eagle-import") (part "1UF_CER_SMD-0402_25V-10%"))
    )
    (comp (ref "D1")
      (value "150mA/75V")
      (footprint "eagle-import:SOD-923F_0402")
      (fields
        (field (name "MFR") "Comchip Technology")
        (field (name "MPN") "CDSQR4148-HF")
        (field (name "CREATOR") "MrSwirlyEyes")
      )
      (libsource (lib "eagle-import") (part "DIODE_GENERAL-PURPOSE_SMD-0402_GP_120MA-75V"))
    )
    (comp (ref "D2")
      (value "150mA/75V")
      (footprint "eagle-import:SOD-923F_0402")
      (fields
        (field (name "MFR") "Comchip Technology")
        (field (name "MPN") "CDSQR4148-HF")
        (field (name "CREATOR") "MrSwirlyEyes")
      )
      (libsource (lib "eagle-import") (part "DIODE_GENERAL-PURPOSE_SMD-0402_GP_120MA-75V"))
    )
    (comp (ref "D3")
      (value "150mA/75V")
      (footprint "eagle-import:SOD-923F_0402")
      (fields
        (field (name "MFR") "Comchip Technology")
        (field (name "MPN") "CDSQR4148-HF")
        (field (name "CREATOR") "MrSwirlyEyes")
      )
      (libsource (lib "eagle-import") (part "DIODE_GENERAL-PURPOSE_SMD-0402_GP_120MA-75V"))
    )
    (comp (ref "D4")
      (value "150mA/75V")
      (footprint "eagle-import:SOD-923F_0402")
      (fields
        (field (name "MFR") "Comchip Technology")
        (field (name "MPN") "CDSQR4148-HF")
        (field (name "CREATOR") "MrSwirlyEyes")
      )
      (libsource (lib "eagle-import") (part "DIODE_GENERAL-PURPOSE_SMD-0402_GP_120MA-75V"))
    )
    (comp (ref "D5")
      (value "150mA/75V")
      (footprint "eagle-import:SOD-923F_0402")
      (fields
        (field (name "MFR") "Comchip Technology")
        (field (name "MPN") "CDSQR4148-HF")
        (field (name "CREATOR") "MrSwirlyEyes")
      )
      (libsource (lib "eagle-import") (part "DIODE_GENERAL-PURPOSE_SMD-0402_GP_120MA-75V"))
    )
    (comp (ref "D8")
      (value "1A/50V")
      (footprint "eagle-import:SOD123F")
      (fields
        (field (name "MFR") "Comchip Technology")
        (field (name "MPN") "CGRKM4001-HF")
        (field (name "CREATOR") "MrSwirlyEyes")
      )
      (libsource (lib "eagle-import") (part "DIODE_GENERAL-PURPOSE_SMD_GP_1A-50V"))
    )
    (comp (ref "D11")
      (value "150mA/75V")
      (footprint "eagle-import:SOD-923F_0402")
      (fields
        (field (name "MFR") "Comchip Technology")
        (field (name "MPN") "CDSQR4148-HF")
        (field (name "CREATOR") "MrSwirlyEyes")
      )
      (libsource (lib "eagle-import") (part "DIODE_GENERAL-PURPOSE_SMD-0402_GP_120MA-75V"))
    )
    (comp (ref "D12")
      (value "150mA/75V")
      (footprint "eagle-import:SOD-923F_0402")
      (fields
        (field (name "MFR") "Comchip Technology")
        (field (name "MPN") "CDSQR4148-HF")
        (field (name "CREATOR") "MrSwirlyEyes")
      )
      (libsource (lib "eagle-import") (part "DIODE_GENERAL-PURPOSE_SMD-0402_GP_120MA-75V"))
    )
    (comp (ref "D13")
      (value "1A/50V")
      (footprint "eagle-import:SOD123F")
      (fields
        (field (name "MFR") "Comchip Technology")
        (field (name "MPN") "CGRKM4001-HF")
        (field (name "CREATOR") "MrSwirlyEyes")
      )
      (libsource (lib "eagle-import") (part "DIODE_GENERAL-PURPOSE_SMD_GP_1A-50V"))
    )
    (comp (ref "D14")
      (value "1A/50V")
      (footprint "eagle-import:SOD123F")
      (fields
        (field (name "MFR") "Comchip Technology")
        (field (name "MPN") "CGRKM4001-HF")
        (field (name "CREATOR") "MrSwirlyEyes")
      )
      (libsource (lib "eagle-import") (part "DIODE_GENERAL-PURPOSE_SMD_GP_1A-50V"))
    )
    (comp (ref "DEMUX1")
      (value "CH16_MUX-DEMUX")
      (footprint "eagle-import:SSOP-24")
      (fields
        (field (name "MFR") "Texas Instruments")
        (field (name "MPN") "CD74HC4067SM96")
        (field (name "CREATOR") "MrSwirlyEyes")
      )
      (libsource (lib "eagle-import") (part "CD74HC4067-SM96_16{colon}1_MUX-DEMUX"))
    )
    (comp (ref "FLEX1")
      (value "10K")
      (footprint "eagle-import:CONNECTOR_FSR")
      (fields
        (field (name "MFR") "Spectra Symbol")
        (field (name "MPN") "FS-L-0055-103-ST?")
        (field (name "CREATOR") "MrSwirlyEyes")
      )
      (libsource (lib "eagle-import") (part "FLEX-SENSOR10K_2.2IN"))
    )
    (comp (ref "FLEX2")
      (value "10K")
      (footprint "eagle-import:CONNECTOR_FSR")
      (fields
        (field (name "MFR") "Spectra Symbol")
        (field (name "MPN") "FS-L-0055-103-ST?")
        (field (name "CREATOR") "MrSwirlyEyes")
      )
      (libsource (lib "eagle-import") (part "FLEX-SENSOR10K_2.2IN"))
    )
    (comp (ref "FLEX3")
      (value "10K")
      (footprint "eagle-import:CONNECTOR_FSR")
      (fields
        (field (name "MFR") "Spectra Symbol")
        (field (name "MPN") "FS-L-0055-103-ST?")
        (field (name "CREATOR") "MrSwirlyEyes")
      )
      (libsource (lib "eagle-import") (part "FLEX-SENSOR10K_2.2IN"))
    )
    (comp (ref "FLEX4")
      (value "10K")
      (footprint "eagle-import:CONNECTOR_FSR")
      (fields
        (field (name "MFR") "Spectra Symbol")
        (field (name "MPN") "FS-L-0055-103-ST?")
        (field (name "CREATOR") "MrSwirlyEyes")
      )
      (libsource (lib "eagle-import") (part "FLEX-SENSOR10K_2.2IN"))
    )
    (comp (ref "FLEX5")
      (value "10K")
      (footprint "eagle-import:CONNECTOR_FSR")
      (fields
        (field (name "MFR") "Spectra Symbol")
        (field (name "MPN") "FS-L-0055-103-ST?")
        (field (name "CREATOR") "MrSwirlyEyes")
      )
      (libsource (lib "eagle-import") (part "FLEX-SENSOR10K_2.2IN"))
    )
    (comp (ref "FLEX6")
      (value "10K")
      (footprint "eagle-import:CONNECTOR_FSR")
      (fields
        (field (name "MFR") "Spectra Symbol")
        (field (name "MPN") "FS-L-0055-103-ST?")
        (field (name "CREATOR") "MrSwirlyEyes")
      )
      (libsource (lib "eagle-import") (part "FLEX-SENSOR10K_2.2IN"))
    )
    (comp (ref "FLEX7")
      (value "10K")
      (footprint "eagle-import:CONNECTOR_FSR")
      (fields
        (field (name "MFR") "Spectra Symbol")
        (field (name "MPN") "FS-L-0055-103-ST?")
        (field (name "CREATOR") "MrSwirlyEyes")
      )
      (libsource (lib "eagle-import") (part "FLEX-SENSOR10K_2.2IN"))
    )
    (comp (ref "FLEX8")
      (value "10K")
      (footprint "eagle-import:CONNECTOR_FSR")
      (fields
        (field (name "MFR") "Spectra Symbol")
        (field (name "MPN") "FS-L-0055-103-ST?")
        (field (name "CREATOR") "MrSwirlyEyes")
      )
      (libsource (lib "eagle-import") (part "FLEX-SENSOR10K_2.2IN"))
    )
    (comp (ref "FLEX9")
      (value "10K")
      (footprint "eagle-import:CONNECTOR_FSR")
      (fields
        (field (name "MFR") "Spectra Symbol")
        (field (name "MPN") "FS-L-0055-103-ST?")
        (field (name "CREATOR") "MrSwirlyEyes")
      )
      (libsource (lib "eagle-import") (part "FLEX-SENSOR10K_2.2IN"))
    )
    (comp (ref "FLEX100")
      (value "10K")
      (footprint "eagle-import:CONNECTOR_FSR")
      (fields
        (field (name "MFR") "Spectra Symbol")
        (field (name "MPN") "FS-L-0055-103-ST?")
        (field (name "CREATOR") "MrSwirlyEyes")
      )
      (libsource (lib "eagle-import") (part "FLEX-SENSOR10K_2.2IN"))
    )
    (comp (ref "HBRIDGE1")
      (value "DRV8837C")
      (footprint "eagle-import:WSON-8-PPAD")
      (fields
        (field (name "MFR") "Texas Instruments")
        (field (name "MPN") "DRV8837CDSGT")
        (field (name "CREATOR") "MrSwirlyEyes")
      )
      (libsource (lib "eagle-import") (part "DRV883X_H-BRIDGE_DRV8837C_1A"))
    )
    (comp (ref "HBRIDGE2")
      (value "DRV8837C")
      (footprint "eagle-import:WSON-8-PPAD")
      (fields
        (field (name "MFR") "Texas Instruments")
        (field (name "MPN") "DRV8837CDSGT")
        (field (name "CREATOR") "MrSwirlyEyes")
      )
      (libsource (lib "eagle-import") (part "DRV883X_H-BRIDGE_DRV8837C_1A"))
    )
    (comp (ref "HBRIDGE3")
      (value "DRV8837C")
      (footprint "eagle-import:WSON-8-PPAD")
      (fields
        (field (name "MFR") "Texas Instruments")
        (field (name "MPN") "DRV8837CDSGT")
        (field (name "CREATOR") "MrSwirlyEyes")
      )
      (libsource (lib "eagle-import") (part "DRV883X_H-BRIDGE_DRV8837C_1A"))
    )
    (comp (ref "HBRIDGE4")
      (value "DRV8837C")
      (footprint "eagle-import:WSON-8-PPAD")
      (fields
        (field (name "MFR") "Texas Instruments")
        (field (name "MPN") "DRV8837CDSGT")
        (field (name "CREATOR") "MrSwirlyEyes")
      )
      (libsource (lib "eagle-import") (part "DRV883X_H-BRIDGE_DRV8837C_1A"))
    )
    (comp (ref "HBRIDGE5")
      (value "DRV8837C")
      (footprint "eagle-import:WSON-8-PPAD")
      (fields
        (field (name "MFR") "Texas Instruments")
        (field (name "MPN") "DRV8837CDSGT")
        (field (name "CREATOR") "MrSwirlyEyes")
      )
      (libsource (lib "eagle-import") (part "DRV883X_H-BRIDGE_DRV8837C_1A"))
    )
    (comp (ref "JP2")
      (value "FTDIPTH-RA")
      (footprint "eagle-import:FTDI_BASIC-6PIN-MALE-RA")
      (fields (field (name "MFR") "Amphenol FCI") (field (name "MPN") "68016-406HLF"))
      (libsource (lib "eagle-import") (part "FTDIPTH-RA"))
    )
    (comp (ref "L3")
      (value "10uH/0.38A")
      (footprint "eagle-import:_SMD-0603")
      (fields
        (field (name "MFR") "Taiyo Yuden")
        (field (name "MPN") "CBMF1608T100K")
        (field (name "CREATOR") "MrSwirlyEyes")
      )
      (libsource (lib "eagle-import") (part "10UH_SMD-0603_0.38A-0.468OHM-10%"))
    )
    (comp (ref "L4")
      (value "10uH/0.38A")
      (footprint "eagle-import:_SMD-0603")
      (fields
        (field (name "MFR") "Taiyo Yuden")
        (field (name "MPN") "CBMF1608T100K")
        (field (name "CREATOR") "MrSwirlyEyes")
      )
      (libsource (lib "eagle-import") (part "10UH_SMD-0603_0.38A-0.468OHM-10%"))
    )
    (comp (ref "LED1")
      (value "GREEN")
      (footprint "eagle-import:LED_SMD-0402")
      (fields
        (field (name "MFR") "Bivar Inc.")
        (field (name "MPN") "SM0402GC")
        (field (name "CREATOR") "MrSwirlyEyes")
      )
      (libsource (lib "eagle-import") (part "LED_SMD-0402_DISCRETE_GREEN"))
    )
    (comp (ref "LED2")
      (value "RED")
      (footprint "eagle-import:LED_SMD-0402")
      (fields
        (field (name "MFR") "Bivar Inc.")
        (field (name "MPN") "SM0402RC")
        (field (name "CREATOR") "MrSwirlyEyes")
      )
      (libsource (lib "eagle-import") (part "LED_SMD-0402_DISCRETE_RED"))
    )
    (comp (ref "LED3")
      (value "BLUE")
      (footprint "eagle-import:LED_SMD-0402")
      (fields
        (field (name "MFR") "Bivar Inc.")
        (field (name "MPN") "SM0402BWC")
        (field (name "CREATOR") "MrSwirlyEyes")
      )
      (libsource (lib "eagle-import") (part "LED_SMD-0402_DISCRETE_BLUE"))
    )
    (comp (ref "MCU")
      (value "ATMEGA128RFA1")
      (footprint "eagle-import:VFQFN-64")
      (fields
        (field (name "MFR") "Atmel")
        (field (name "MPN") "ATMEGA128RFA1-ZU ")
        (field (name "CREATOR") "Kenmei")
      )
      (libsource (lib "eagle-import") (part "ATMEGA128RFA1_VFQFN-64_EXPOSED-PAD"))
    )
    (comp (ref "NOISE_BR")
      (value "2PT_GND_TIE")
      (footprint "eagle-import:2PT_GND_TIE")
      (libsource (lib "eagle-import") (part "2PT_GND_TIE"))
    )
    (comp (ref "PWM_DRIVER1")
      (value "PCA9685")
      (footprint "eagle-import:TSSOP-28")
      (fields
        (field (name "MFR") "NXP USA Inc.")
        (field (name "MPN") "PCA9685PW,118")
        (field (name "CREATOR") "MrSwirlyEyes")
      )
      (libsource (lib "eagle-import") (part "PCA9685_16-CH_12-BIT_PWM-DRIVER"))
    )
    (comp (ref "Q1")
      (value "MCH3474 4A/30V/50mΩ")
      (footprint "eagle-import:SC-70FL_MCPH3")
      (fields
        (field (name "MFR") "ON Semiconductor")
        (field (name "MPN") "MCH3474-TL-W")
        (field (name "CREATOR") "Kenmei")
      )
      (libsource (lib "eagle-import") (part "POWER_NCHAN_MCH3474"))
    )
    (comp (ref "Q2")
      (value "MCH3474 4A/30V/50mΩ")
      (footprint "eagle-import:SC-70FL_MCPH3")
      (fields
        (field (name "MFR") "ON Semiconductor")
        (field (name "MPN") "MCH3474-TL-W")
        (field (name "CREATOR") "Kenmei")
      )
      (libsource (lib "eagle-import") (part "POWER_NCHAN_MCH3474"))
    )
    (comp (ref "Q3")
      (value "MCH3474 4A/30V/50mΩ")
      (footprint "eagle-import:SC-70FL_MCPH3")
      (fields
        (field (name "MFR") "ON Semiconductor")
        (field (name "MPN") "MCH3474-TL-W")
        (field (name "CREATOR") "Kenmei")
      )
      (libsource (lib "eagle-import") (part "POWER_NCHAN_MCH3474"))
    )
    (comp (ref "Q4")
      (value "MCH3474 4A/30V/50mΩ")
      (footprint "eagle-import:SC-70FL_MCPH3")
      (fields
        (field (name "MFR") "ON Semiconductor")
        (field (name "MPN") "MCH3474-TL-W")
        (field (name "CREATOR") "Kenmei")
      )
      (libsource (lib "eagle-import") (part "POWER_NCHAN_MCH3474"))
    )
    (comp (ref "Q5")
      (value "MCH3474 4A/30V/50mΩ")
      (footprint "eagle-import:SC-70FL_MCPH3")
      (fields
        (field (name "MFR") "ON Semiconductor")
        (field (name "MPN") "MCH3474-TL-W")
        (field (name "CREATOR") "Kenmei")
      )
      (libsource (lib "eagle-import") (part "POWER_NCHAN_MCH3474"))
    )
    (comp (ref "Q6")
      (value "MCH3474 4A/30V/50mΩ")
      (footprint "eagle-import:SC-70FL_MCPH3")
      (fields
        (field (name "MFR") "ON Semiconductor")
        (field (name "MPN") "MCH3474-TL-W")
        (field (name "CREATOR") "Kenmei")
      )
      (libsource (lib "eagle-import") (part "POWER_NCHAN_MCH3474"))
    )
    (comp (ref "R1")
      (value "10KΩ")
      (footprint "eagle-import:RESISTOR_SMD-0402")
      (fields
        (field (name "MFR") "Yageo")
        (field (name "MPN") "RC0402JR-0710KL")
        (field (name "CREATOR") "MrSwirlyEyes")
      )
      (libsource (lib "eagle-import") (part "10KΩ_SMD-0402_1/16W-5%"))
    )
    (comp (ref "R2")
      (value "10KΩ")
      (footprint "eagle-import:RESISTOR_SMD-0402")
      (fields
        (field (name "MFR") "Yageo")
        (field (name "MPN") "RC0402JR-0710KL")
        (field (name "CREATOR") "MrSwirlyEyes")
      )
      (libsource (lib "eagle-import") (part "10KΩ_SMD-0402_1/16W-5%"))
    )
    (comp (ref "R3")
      (value "10KΩ")
      (footprint "eagle-import:RESISTOR_SMD-0402")
      (fields
        (field (name "MFR") "Yageo")
        (field (name "MPN") "RC0402JR-0710KL")
        (field (name "CREATOR") "MrSwirlyEyes")
      )
      (libsource (lib "eagle-import") (part "10KΩ_SMD-0402_1/16W-5%"))
    )
    (comp (ref "R4")
      (value "10KΩ")
      (footprint "eagle-import:RESISTOR_SMD-0402")
      (fields
        (field (name "MFR") "Yageo")
        (field (name "MPN") "RC0402JR-0710KL")
        (field (name "CREATOR") "MrSwirlyEyes")
      )
      (libsource (lib "eagle-import") (part "10KΩ_SMD-0402_1/16W-5%"))
    )
    (comp (ref "R5")
      (value "10KΩ")
      (footprint "eagle-import:RESISTOR_SMD-0402")
      (fields
        (field (name "MFR") "Yageo")
        (field (name "MPN") "RC0402JR-0710KL")
        (field (name "CREATOR") "MrSwirlyEyes")
      )
      (libsource (lib "eagle-import") (part "10KΩ_SMD-0402_1/16W-5%"))
    )
    (comp (ref "R6")
      (value "100Ω")
      (footprint "eagle-import:RESISTOR_SMD-0402")
      (fields
        (field (name "MFR") "Yageo")
        (field (name "MPN") "RC0402JR-07100RL")
        (field (name "CREATOR") "MrSwirlyEyes")
      )
      (libsource (lib "eagle-import") (part "100Ω_SMD-0402_1/16W-5%"))
    )
    (comp (ref "R7")
      (value "100Ω")
      (footprint "eagle-import:RESISTOR_SMD-0402")
      (fields
        (field (name "MFR") "Yageo")
        (field (name "MPN") "RC0402JR-07100RL")
        (field (name "CREATOR") "MrSwirlyEyes")
      )
      (libsource (lib "eagle-import") (part "100Ω_SMD-0402_1/16W-5%"))
    )
    (comp (ref "R8")
      (value "100Ω")
      (footprint "eagle-import:RESISTOR_SMD-0402")
      (fields
        (field (name "MFR") "Yageo")
        (field (name "MPN") "RC0402JR-07100RL")
        (field (name "CREATOR") "MrSwirlyEyes")
      )
      (libsource (lib "eagle-import") (part "100Ω_SMD-0402_1/16W-5%"))
    )
    (comp (ref "R9")
      (value "100Ω")
      (footprint "eagle-import:RESISTOR_SMD-0402")
      (fields
        (field (name "MFR") "Yageo")
        (field (name "MPN") "RC0402JR-07100RL")
        (field (name "CREATOR") "MrSwirlyEyes")
      )
      (libsource (lib "eagle-import") (part "100Ω_SMD-0402_1/16W-5%"))
    )
    (comp (ref "R10")
      (value "100Ω")
      (footprint "eagle-import:RESISTOR_SMD-0402")
      (fields
        (field (name "MFR") "Yageo")
        (field (name "MPN") "RC0402JR-07100RL")
        (field (name "CREATOR") "MrSwirlyEyes")
      )
      (libsource (lib "eagle-import") (part "100Ω_SMD-0402_1/16W-5%"))
    )
    (comp (ref "R11")
      (value "47KΩ")
      (footprint "eagle-import:RESISTOR_SMD-0402")
      (fields
        (field (name "MFR") "Yageo")
        (field (name "MPN") "RC0402JR-0747KL")
        (field (name "CREATOR") "MrSwirlyEyes")
      )
      (libsource (lib "eagle-import") (part "47KΩ_SMD-0402_1/16W-5%"))
    )
    (comp (ref "R12")
      (value "10KΩ")
      (footprint "eagle-import:RESISTOR_SMD-0402")
      (fields
        (field (name "MFR") "Yageo")
        (field (name "MPN") "RC0402JR-0710KL")
        (field (name "CREATOR") "MrSwirlyEyes")
      )
      (libsource (lib "eagle-import") (part "10KΩ_SMD-0402_1/16W-5%"))
    )
    (comp (ref "R13")
      (value "100Ω")
      (footprint "eagle-import:RESISTOR_SMD-0402")
      (fields
        (field (name "MFR") "Yageo")
        (field (name "MPN") "RC0402JR-07100RL")
        (field (name "CREATOR") "MrSwirlyEyes")
      )
      (libsource (lib "eagle-import") (part "100Ω_SMD-0402_1/16W-5%"))
    )
    (comp (ref "R14")
      (value "10KΩ")
      (footprint "eagle-import:RESISTOR_SMD-0402")
      (fields
        (field (name "MFR") "Yageo")
        (field (name "MPN") "RC0402JR-0710KL")
        (field (name "CREATOR") "MrSwirlyEyes")
      )
      (libsource (lib "eagle-import") (part "10KΩ_SMD-0402_1/16W-5%"))
    )
    (comp (ref "R15")
      (value "100Ω")
      (footprint "eagle-import:RESISTOR_SMD-0402")
      (fields
        (field (name "MFR") "Yageo")
        (field (name "MPN") "RC0402JR-07100RL")
        (field (name "CREATOR") "MrSwirlyEyes")
      )
      (libsource (lib "eagle-import") (part "100Ω_SMD-0402_1/16W-5%"))
    )
    (comp (ref "R16")
      (value "10KΩ")
      (footprint "eagle-import:RESISTOR_SMD-0402")
      (fields
        (field (name "MFR") "Yageo")
        (field (name "MPN") "RC0402JR-0710KL")
        (field (name "CREATOR") "MrSwirlyEyes")
      )
      (libsource (lib "eagle-import") (part "10KΩ_SMD-0402_1/16W-5%"))
    )
    (comp (ref "R17")
      (value "100Ω")
      (footprint "eagle-import:RESISTOR_SMD-0402")
      (fields
        (field (name "MFR") "Yageo")
        (field (name "MPN") "RC0402JR-07100RL")
        (field (name "CREATOR") "MrSwirlyEyes")
      )
      (libsource (lib "eagle-import") (part "100Ω_SMD-0402_1/16W-5%"))
    )
    (comp (ref "R18")
      (value "10KΩ")
      (footprint "eagle-import:RESISTOR_SMD-0402")
      (fields
        (field (name "MFR") "Yageo")
        (field (name "MPN") "RC0402JR-0710KL")
        (field (name "CREATOR") "MrSwirlyEyes")
      )
      (libsource (lib "eagle-import") (part "10KΩ_SMD-0402_1/16W-5%"))
    )
    (comp (ref "R19")
      (value "100Ω")
      (footprint "eagle-import:RESISTOR_SMD-0402")
      (fields
        (field (name "MFR") "Yageo")
        (field (name "MPN") "RC0402JR-07100RL")
        (field (name "CREATOR") "MrSwirlyEyes")
      )
      (libsource (lib "eagle-import") (part "100Ω_SMD-0402_1/16W-5%"))
    )
    (comp (ref "R20")
      (value "10KΩ")
      (footprint "eagle-import:RESISTOR_SMD-0402")
      (fields
        (field (name "MFR") "Yageo")
        (field (name "MPN") "RC0402JR-0710KL")
        (field (name "CREATOR") "MrSwirlyEyes")
      )
      (libsource (lib "eagle-import") (part "10KΩ_SMD-0402_1/16W-5%"))
    )
    (comp (ref "R21")
      (value "100Ω")
      (footprint "eagle-import:RESISTOR_SMD-0402")
      (fields
        (field (name "MFR") "Yageo")
        (field (name "MPN") "RC0402JR-07100RL")
        (field (name "CREATOR") "MrSwirlyEyes")
      )
      (libsource (lib "eagle-import") (part "100Ω_SMD-0402_1/16W-5%"))
    )
    (comp (ref "R22")
      (value "10KΩ")
      (footprint "eagle-import:RESISTOR_SMD-0402")
      (fields
        (field (name "MFR") "Yageo")
        (field (name "MPN") "RC0402JR-0710KL")
        (field (name "CREATOR") "MrSwirlyEyes")
      )
      (libsource (lib "eagle-import") (part "10KΩ_SMD-0402_1/16W-5%"))
    )
    (comp (ref "R23")
      (value "100Ω")
      (footprint "eagle-import:RESISTOR_SMD-0402")
      (fields
        (field (name "MFR") "Yageo")
        (field (name "MPN") "RC0402JR-07100RL")
        (field (name "CREATOR") "MrSwirlyEyes")
      )
      (libsource (lib "eagle-import") (part "100Ω_SMD-0402_1/16W-5%"))
    )
    (comp (ref "R24")
      (value "10KΩ")
      (footprint "eagle-import:RESISTOR_SMD-0402")
      (fields
        (field (name "MFR") "Yageo")
        (field (name "MPN") "RC0402JR-0710KL")
        (field (name "CREATOR") "MrSwirlyEyes")
      )
      (libsource (lib "eagle-import") (part "10KΩ_SMD-0402_1/16W-5%"))
    )
    (comp (ref "R25")
      (value "100Ω")
      (footprint "eagle-import:RESISTOR_SMD-0402")
      (fields
        (field (name "MFR") "Yageo")
        (field (name "MPN") "RC0402JR-07100RL")
        (field (name "CREATOR") "MrSwirlyEyes")
      )
      (libsource (lib "eagle-import") (part "100Ω_SMD-0402_1/16W-5%"))
    )
    (comp (ref "R26")
      (value "10KΩ")
      (footprint "eagle-import:RESISTOR_SMD-0402")
      (fields
        (field (name "MFR") "Yageo")
        (field (name "MPN") "RC0402JR-0710KL")
        (field (name "CREATOR") "MrSwirlyEyes")
      )
      (libsource (lib "eagle-import") (part "10KΩ_SMD-0402_1/16W-5%"))
    )
    (comp (ref "R27")
      (value "100Ω")
      (footprint "eagle-import:RESISTOR_SMD-0402")
      (fields
        (field (name "MFR") "Yageo")
        (field (name "MPN") "RC0402JR-07100RL")
        (field (name "CREATOR") "MrSwirlyEyes")
      )
      (libsource (lib "eagle-import") (part "100Ω_SMD-0402_1/16W-5%"))
    )
    (comp (ref "R28")
      (value "10KΩ")
      (footprint "eagle-import:RESISTOR_SMD-0402")
      (fields
        (field (name "MFR") "Yageo")
        (field (name "MPN") "RC0402JR-0710KL")
        (field (name "CREATOR") "MrSwirlyEyes")
      )
      (libsource (lib "eagle-import") (part "10KΩ_SMD-0402_1/16W-5%"))
    )
    (comp (ref "R29")
      (value "100Ω")
      (footprint "eagle-import:RESISTOR_SMD-0402")
      (fields
        (field (name "MFR") "Yageo")
        (field (name "MPN") "RC0402JR-07100RL")
        (field (name "CREATOR") "MrSwirlyEyes")
      )
      (libsource (lib "eagle-import") (part "100Ω_SMD-0402_1/16W-5%"))
    )
    (comp (ref "R30")
      (value "10KΩ")
      (footprint "eagle-import:RESISTOR_SMD-0402")
      (fields
        (field (name "MFR") "Yageo")
        (field (name "MPN") "RC0402JR-0710KL")
        (field (name "CREATOR") "MrSwirlyEyes")
      )
      (libsource (lib "eagle-import") (part "10KΩ_SMD-0402_1/16W-5%"))
    )
    (comp (ref "R31")
      (value "100Ω")
      (footprint "eagle-import:RESISTOR_SMD-0402")
      (fields
        (field (name "MFR") "Yageo")
        (field (name "MPN") "RC0402JR-07100RL")
        (field (name "CREATOR") "MrSwirlyEyes")
      )
      (libsource (lib "eagle-import") (part "100Ω_SMD-0402_1/16W-5%"))
    )
    (comp (ref "R32")
      (value "10KΩ")
      (footprint "eagle-import:RESISTOR_SMD-0402")
      (fields
        (field (name "MFR") "Yageo")
        (field (name "MPN") "RC0402JR-0710KL")
        (field (name "CREATOR") "MrSwirlyEyes")
      )
      (libsource (lib "eagle-import") (part "10KΩ_SMD-0402_1/16W-5%"))
    )
    (comp (ref "R33")
      (value "100Ω")
      (footprint "eagle-import:RESISTOR_SMD-0402")
      (fields
        (field (name "MFR") "Yageo")
        (field (name "MPN") "RC0402JR-07100RL")
        (field (name "CREATOR") "MrSwirlyEyes")
      )
      (libsource (lib "eagle-import") (part "100Ω_SMD-0402_1/16W-5%"))
    )
    (comp (ref "R34")
      (value "47KΩ")
      (footprint "eagle-import:RESISTOR_SMD-0402")
      (fields
        (field (name "MFR") "Yageo")
        (field (name "MPN") "RC0402JR-0747KL")
        (field (name "CREATOR") "MrSwirlyEyes")
      )
      (libsource (lib "eagle-import") (part "47KΩ_SMD-0402_1/16W-5%"))
    )
    (comp (ref "R35")
      (value "47KΩ")
      (footprint "eagle-import:RESISTOR_SMD-0402")
      (fields
        (field (name "MFR") "Yageo")
        (field (name "MPN") "RC0402JR-0747KL")
        (field (name "CREATOR") "MrSwirlyEyes")
      )
      (libsource (lib "eagle-import") (part "47KΩ_SMD-0402_1/16W-5%"))
    )
    (comp (ref "R36")
      (value "47KΩ")
      (footprint "eagle-import:RESISTOR_SMD-0402")
      (fields
        (field (name "MFR") "Yageo")
        (field (name "MPN") "RC0402JR-0747KL")
        (field (name "CREATOR") "MrSwirlyEyes")
      )
      (libsource (lib "eagle-import") (part "47KΩ_SMD-0402_1/16W-5%"))
    )
    (comp (ref "R37")
      (value "47KΩ")
      (footprint "eagle-import:RESISTOR_SMD-0402")
      (fields
        (field (name "MFR") "Yageo")
        (field (name "MPN") "RC0402JR-0747KL")
        (field (name "CREATOR") "MrSwirlyEyes")
      )
      (libsource (lib "eagle-import") (part "47KΩ_SMD-0402_1/16W-5%"))
    )
    (comp (ref "R38")
      (value "47KΩ")
      (footprint "eagle-import:RESISTOR_SMD-0402")
      (fields
        (field (name "MFR") "Yageo")
        (field (name "MPN") "RC0402JR-0747KL")
        (field (name "CREATOR") "MrSwirlyEyes")
      )
      (libsource (lib "eagle-import") (part "47KΩ_SMD-0402_1/16W-5%"))
    )
    (comp (ref "R39")
      (value "47KΩ")
      (footprint "eagle-import:RESISTOR_SMD-0402")
      (fields
        (field (name "MFR") "Yageo")
        (field (name "MPN") "RC0402JR-0747KL")
        (field (name "CREATOR") "MrSwirlyEyes")
      )
      (libsource (lib "eagle-import") (part "47KΩ_SMD-0402_1/16W-5%"))
    )
    (comp (ref "R40")
      (value "4.7KΩ")
      (footprint "eagle-import:RESISTOR_SMD-0402")
      (fields
        (field (name "MFR") "Yageo")
        (field (name "MPN") "RC0402JR-074K7L")
        (field (name "CREATOR") "MrSwirlyEyes")
      )
      (libsource (lib "eagle-import") (part "4.7KΩ_SMD-0402_1/16W-5%"))
    )
    (comp (ref "R41")
      (value "4.7KΩ")
      (footprint "eagle-import:RESISTOR_SMD-0402")
      (fields
        (field (name "MFR") "Yageo")
        (field (name "MPN") "RC0402JR-074K7L")
        (field (name "CREATOR") "MrSwirlyEyes")
      )
      (libsource (lib "eagle-import") (part "4.7KΩ_SMD-0402_1/16W-5%"))
    )
    (comp (ref "R42")
      (value "47KΩ")
      (footprint "eagle-import:RESISTOR_SMD-0402")
      (fields
        (field (name "MFR") "Yageo")
        (field (name "MPN") "RC0402JR-0747KL")
        (field (name "CREATOR") "MrSwirlyEyes")
      )
      (libsource (lib "eagle-import") (part "47KΩ_SMD-0402_1/16W-5%"))
    )
    (comp (ref "R43")
      (value "47KΩ")
      (footprint "eagle-import:RESISTOR_SMD-0402")
      (fields
        (field (name "MFR") "Yageo")
        (field (name "MPN") "RC0402JR-0747KL")
        (field (name "CREATOR") "MrSwirlyEyes")
      )
      (libsource (lib "eagle-import") (part "47KΩ_SMD-0402_1/16W-5%"))
    )
    (comp (ref "R44")
      (value "47KΩ")
      (footprint "eagle-import:RESISTOR_SMD-0402")
      (fields
        (field (name "MFR") "Yageo")
        (field (name "MPN") "RC0402JR-0747KL")
        (field (name "CREATOR") "MrSwirlyEyes")
      )
      (libsource (lib "eagle-import") (part "47KΩ_SMD-0402_1/16W-5%"))
    )
    (comp (ref "R46")
      (value "10KΩ")
      (footprint "eagle-import:RESISTOR_SMD-0402")
      (fields
        (field (name "MFR") "Yageo")
        (field (name "MPN") "RC0402JR-0710KL")
        (field (name "CREATOR") "MrSwirlyEyes")
      )
      (libsource (lib "eagle-import") (part "10KΩ_SMD-0402_1/16W-5%"))
    )
    (comp (ref "R47")
      (value "10KΩ")
      (footprint "eagle-import:RESISTOR_SMD-0402")
      (fields
        (field (name "MFR") "Yageo")
        (field (name "MPN") "RC0402JR-0710KL")
        (field (name "CREATOR") "MrSwirlyEyes")
      )
      (libsource (lib "eagle-import") (part "10KΩ_SMD-0402_1/16W-5%"))
    )
    (comp (ref "R48")
      (value "2KΩ")
      (footprint "eagle-import:RESISTOR_SMD-0402")
      (fields
        (field (name "MFR") "Yageo")
        (field (name "MPN") "RC0402JR-072KL")
        (field (name "CREATOR") "MrSwirlyEyes")
      )
      (libsource (lib "eagle-import") (part "2KΩ_SMD-0402_1/16W-5%"))
    )
    (comp (ref "R49")
      (value "1KΩ")
      (footprint "eagle-import:RESISTOR_SMD-0402")
      (fields
        (field (name "MFR") "Yageo")
        (field (name "MPN") "RC0402JR-071KL")
        (field (name "CREATOR") "MrSwirlyEyes")
      )
      (libsource (lib "eagle-import") (part "1KΩ_SMD-0402_1/16W-5%"))
    )
    (comp (ref "SW1")
      (value "4A/28V")
      (footprint "eagle-import:SW_SLIDE_RA_SPDT_4A-28V_L12.7-W9.5")
      (fields
        (field (name "MFR") "E-Switch")
        (field (name "MPN") "500SSP1S1M6QEA")
        (field (name "CREATOR") "MrSwirlyEyes")
      )
      (libsource (lib "eagle-import") (part "SWITCH_SPDT_RA_PTH_4A-28V_L12.7-W9.5"))
    )
    (comp (ref "TEC1")
      (value "PELTIER")
      (footprint "eagle-import:CONNECTOR_PELTIER")
      (fields
        (field (name "MFR") "Marlow Industries, Inc.")
        (field (name "MPN") "NL1025T-01AC")
        (field (name "CREATOR") "MrSwirlyEyes")
      )
      (libsource (lib "eagle-import") (part "PELTIER-TECNL1025T_1.8A-4.4V_L10.7-W8.8-H2"))
    )
    (comp (ref "TEC2")
      (value "PELTIER")
      (footprint "eagle-import:CONNECTOR_PELTIER")
      (fields
        (field (name "MFR") "Marlow Industries, Inc.")
        (field (name "MPN") "NL1025T-01AC")
        (field (name "CREATOR") "MrSwirlyEyes")
      )
      (libsource (lib "eagle-import") (part "PELTIER-TECNL1025T_1.8A-4.4V_L10.7-W8.8-H2"))
    )
    (comp (ref "TEC3")
      (value "PELTIER")
      (footprint "eagle-import:CONNECTOR_PELTIER")
      (fields
        (field (name "MFR") "Marlow Industries, Inc.")
        (field (name "MPN") "NL1025T-01AC")
        (field (name "CREATOR") "MrSwirlyEyes")
      )
      (libsource (lib "eagle-import") (part "PELTIER-TECNL1025T_1.8A-4.4V_L10.7-W8.8-H2"))
    )
    (comp (ref "TEC4")
      (value "PELTIER")
      (footprint "eagle-import:CONNECTOR_PELTIER")
      (fields
        (field (name "MFR") "Marlow Industries, Inc.")
        (field (name "MPN") "NL1025T-01AC")
        (field (name "CREATOR") "MrSwirlyEyes")
      )
      (libsource (lib "eagle-import") (part "PELTIER-TECNL1025T_1.8A-4.4V_L10.7-W8.8-H2"))
    )
    (comp (ref "TEC5")
      (value "PELTIER")
      (footprint "eagle-import:CONNECTOR_PELTIER")
      (fields
        (field (name "MFR") "Marlow Industries, Inc.")
        (field (name "MPN") "NL1025T-01AC")
        (field (name "CREATOR") "MrSwirlyEyes")
      )
      (libsource (lib "eagle-import") (part "PELTIER-TECNL1025T_1.8A-4.4V_L10.7-W8.8-H2"))
    )
    (comp (ref "VIBE1")
      (value "VIBE_MOTOR")
      (footprint "eagle-import:CONNECTOR_VIBE-MOTOR")
      (fields
        (field (name "MFR") "Jinlong Machinery & Electronics, Inc.")
        (field (name "MPN") "C0825B002F")
        (field (name "CREATOR") "MrSwirlyEyes")
      )
      (libsource (lib "eagle-import") (part "VIBE_MOTOR_100MA/3V"))
    )
    (comp (ref "VIBE2")
      (value "VIBE_MOTOR")
      (footprint "eagle-import:CONNECTOR_VIBE-MOTOR")
      (fields
        (field (name "MFR") "Jinlong Machinery & Electronics, Inc.")
        (field (name "MPN") "C0825B002F")
        (field (name "CREATOR") "MrSwirlyEyes")
      )
      (libsource (lib "eagle-import") (part "VIBE_MOTOR_100MA/3V"))
    )
    (comp (ref "VIBE3")
      (value "VIBE_MOTOR")
      (footprint "eagle-import:CONNECTOR_VIBE-MOTOR")
      (fields
        (field (name "MFR") "Jinlong Machinery & Electronics, Inc.")
        (field (name "MPN") "C0825B002F")
        (field (name "CREATOR") "MrSwirlyEyes")
      )
      (libsource (lib "eagle-import") (part "VIBE_MOTOR_100MA/3V"))
    )
    (comp (ref "VIBE4")
      (value "VIBE_MOTOR")
      (footprint "eagle-import:CONNECTOR_VIBE-MOTOR")
      (fields
        (field (name "MFR") "Jinlong Machinery & Electronics, Inc.")
        (field (name "MPN") "C0825B002F")
        (field (name "CREATOR") "MrSwirlyEyes")
      )
      (libsource (lib "eagle-import") (part "VIBE_MOTOR_100MA/3V"))
    )
    (comp (ref "VIBE5")
      (value "VIBE_MOTOR")
      (footprint "eagle-import:CONNECTOR_VIBE-MOTOR")
      (fields
        (field (name "MFR") "Jinlong Machinery & Electronics, Inc.")
        (field (name "MPN") "C0825B002F")
        (field (name "CREATOR") "MrSwirlyEyes")
      )
      (libsource (lib "eagle-import") (part "VIBE_MOTOR_100MA/3V"))
    )
    (comp (ref "VIBE6")
      (value "VIBE_MOTOR")
      (footprint "eagle-import:CONNECTOR_VIBE-MOTOR")
      (fields
        (field (name "MFR") "Jinlong Machinery & Electronics, Inc.")
        (field (name "MPN") "C0825B002F")
        (field (name "CREATOR") "MrSwirlyEyes")
      )
      (libsource (lib "eagle-import") (part "VIBE_MOTOR_100MA/3V"))
    )
    (comp (ref "VREG1")
      (value "1A/3.3V")
      (footprint "eagle-import:SOIC-8_W3.9MM")
      (fields
        (field (name "MFR") "Texas Instruments")
        (field (name "MPN") "TPS76833QDR")
        (field (name "CREATOR") "MrSwirlyEyes")
      )
      (libsource (lib "eagle-import") (part "VREG_TPS76833_ULDO_FAST-TRANSIENT_1A-3.3VTPS76833QDR_1A-3.3V"))
    )
    (comp (ref "VREG6")
      (value "TL1963A-33 1.5A/3.3V")
      (footprint "eagle-import:SOT223-4")
      (fields
        (field (name "MFR") "Texas Instruments")
        (field (name "MPN") "TL1963A-33DCYR")
        (field (name "CREATOR") "MrSwirlyEyes")
      )
      (libsource (lib "eagle-import") (part "VREG_LINEAR_FIXED_TL1963A-33_LDO_1.5A-3.3V"))
    )
    (comp (ref "VREG7")
      (value "3A/1.8V")
      (footprint "eagle-import:DDPAK-5")
      (fields
        (field (name "MFR") "Linear Technology")
        (field (name "MPN") "LT1764EQ-1.8#PBF")
        (field (name "CREATOR") "MrSwirlyEyes")
      )
      (libsource (lib "eagle-import") (part "VREG_LT1764EQ_ULDO_FAST-TRANSIENT_LT1764EQ-1.8_3A-1.8V"))
    )
    (comp (ref "Y2")
      (value "16MHz")
      (footprint "eagle-import:CRYSTAL-SMD-5X3")
      (fields (field (name "MFR") "Abracon LLC") (field (name "MPN") "ABM3B-16.000MHZ-B2-T"))
      (libsource (lib "eagle-import") (part "CRYSTAL_ABM3B_16MHZ_18PF"))
    )
  )
  (nets
    (net (code "1") (name "1.8V") (class "Default")
      (node (ref "C10") (pin "1") (pinfunction "1_1") (pintype "passive"))
      (node (ref "C13") (pin "1") (pinfunction "1_1") (pintype "passive"))
      (node (ref "C14") (pin "1") (pinfunction "1_1") (pintype "passive"))
      (node (ref "C17") (pin "1") (pinfunction "1_1") (pintype "passive"))
      (node (ref "C18") (pin "1") (pinfunction "1_1") (pintype "passive"))
      (node (ref "C21") (pin "1") (pinfunction "1_1") (pintype "passive"))
      (node (ref "C22") (pin "1") (pinfunction "1_1") (pintype "passive"))
      (node (ref "C26") (pin "1") (pinfunction "1_1") (pintype "passive"))
      (node (ref "C27") (pin "1") (pinfunction "1_1") (pintype "passive"))
      (node (ref "C39") (pin "1") (pinfunction "1_1") (pintype "passive"))
      (node (ref "C40") (pin "1") (pinfunction "1_1") (pintype "passive"))
      (node (ref "C42") (pin "1") (pinfunction "1_1") (pintype "passive"))
      (node (ref "C9") (pin "1") (pinfunction "1_1") (pintype "passive"))
      (node (ref "D14") (pin "A") (pinfunction "A_A") (pintype "passive"))
      (node (ref "HBRIDGE1") (pin "1") (pinfunction "VM_1") (pintype "passive"))
      (node (ref "HBRIDGE2") (pin "1") (pinfunction "VM_1") (pintype "passive"))
      (node (ref "HBRIDGE3") (pin "1") (pinfunction "VM_1") (pintype "passive"))
      (node (ref "HBRIDGE4") (pin "1") (pinfunction "VM_1") (pintype "passive"))
      (node (ref "HBRIDGE5") (pin "1") (pinfunction "VM_1") (pintype "passive"))
      (node (ref "VREG7") (pin "4") (pinfunction "VOUT_4") (pintype "bidirectional"))
      (node (ref "VREG7") (pin "5") (pinfunction "SENSE_5") (pintype "bidirectional"))
    )
    (net (code "2") (name "3.3V") (class "Default")
      (node (ref "C1") (pin "1") (pinfunction "1_1") (pintype "passive"))
      (node (ref "C3") (pin "1") (pinfunction "1_1") (pintype "passive"))
      (node (ref "C36") (pin "1") (pinfunction "1_1") (pintype "passive"))
      (node (ref "C4") (pin "1") (pinfunction "1_1") (pintype "passive"))
      (node (ref "C41") (pin "1") (pinfunction "1_1") (pintype "passive"))
      (node (ref "C43") (pin "1") (pinfunction "1_1") (pintype "passive"))
      (node (ref "C5") (pin "1") (pinfunction "1_1") (pintype "passive"))
      (node (ref "C6") (pin "1") (pinfunction "1_1") (pintype "passive"))
      (node (ref "C7") (pin "1") (pinfunction "1_1") (pintype "passive"))
      (node (ref "D1") (pin "K") (pinfunction "K_K") (pintype "passive"))
      (node (ref "D12") (pin "K") (pinfunction "K_K") (pintype "passive"))
      (node (ref "D13") (pin "A") (pinfunction "A_A") (pintype "passive"))
      (node (ref "D2") (pin "K") (pinfunction "K_K") (pintype "passive"))
      (node (ref "D3") (pin "K") (pinfunction "K_K") (pintype "passive"))
      (node (ref "D4") (pin "K") (pinfunction "K_K") (pintype "passive"))
      (node (ref "D5") (pin "K") (pinfunction "K_K") (pintype "passive"))
      (node (ref "VIBE1") (pin "1") (pinfunction "+_1") (pintype "passive"))
      (node (ref "VIBE2") (pin "1") (pinfunction "+_1") (pintype "passive"))
      (node (ref "VIBE3") (pin "1") (pinfunction "+_1") (pintype "passive"))
      (node (ref "VIBE4") (pin "1") (pinfunction "+_1") (pintype "passive"))
      (node (ref "VIBE5") (pin "1") (pinfunction "+_1") (pintype "passive"))
      (node (ref "VIBE6") (pin "1") (pinfunction "+_1") (pintype "passive"))
      (node (ref "VREG6") (pin "3") (pinfunction "VO_3") (pintype "bidirectional"))
    )
    (net (code "3") (name "A0") (class "Default")
      (node (ref "MCU") (pin "63") (pinfunction "(ADC0/A0*)PF0_63") (pintype "bidirectional"))
    )
    (net (code "4") (name "A1") (class "Default")
      (node (ref "DEMUX1") (pin "1") (pinfunction "SIG_1") (pintype "passive"))
      (node (ref "MCU") (pin "64") (pinfunction "(ADC1/A1*)PF1_64") (pintype "bidirectional"))
    )
    (net (code "5") (name "A2") (class "Default")
      (node (ref "MCU") (pin "1") (pinfunction "(ADC2/DIG2/A2*)PF2_1") (pintype "bidirectional"))
    )
    (net (code "6") (name "A3") (class "Default")
      (node (ref "MCU") (pin "2") (pinfunction "(ADC3/DIG4/A3*)PF3_2") (pintype "bidirectional"))
    )
    (net (code "7") (name "A4") (class "Default")
      (node (ref "MCU") (pin "3") (pinfunction "(ADC4/TCK/A4*)PF4_3") (pintype "bidirectional"))
    )
    (net (code "8") (name "A5") (class "Default")
      (node (ref "MCU") (pin "4") (pinfunction "(ADC5/TMS/A5*)PF5_4") (pintype "bidirectional"))
    )
    (net (code "9") (name "A6") (class "Default")
      (node (ref "MCU") (pin "5") (pinfunction "(ADC6/TDO/A6*)PF6_5") (pintype "bidirectional"))
    )
    (net (code "10") (name "A7") (class "Default")
      (node (ref "MCU") (pin "6") (pinfunction "(ADC7/TDI/A7*)PF7_6") (pintype "bidirectional"))
    )
    (net (code "11") (name "AGND") (class "Default")
      (node (ref "ANALOG_BR") (pin "P$2") (pinfunction "P$2_P$2") (pintype "bidirectional"))
      (node (ref "C100") (pin "2") (pinfunction "2_2") (pintype "passive"))
      (node (ref "C122") (pin "2") (pinfunction "2_2") (pintype "passive"))
      (node (ref "C134") (pin "2") (pinfunction "2_2") (pintype "passive"))
      (node (ref "C135") (pin "2") (pinfunction "2_2") (pintype "passive"))
      (node (ref "C136") (pin "2") (pinfunction "2_2") (pintype "passive"))
      (node (ref "C30") (pin "2") (pinfunction "2_2") (pintype "passive"))
      (node (ref "C31") (pin "2") (pinfunction "2_2") (pintype "passive"))
      (node (ref "C32") (pin "2") (pinfunction "2_2") (pintype "passive"))
      (node (ref "C33") (pin "2") (pinfunction "2_2") (pintype "passive"))
      (node (ref "C34") (pin "2") (pinfunction "2_2") (pintype "passive"))
      (node (ref "C47") (pin "2") (pinfunction "2_2") (pintype "passive"))
      (node (ref "C48") (pin "2") (pinfunction "2_2") (pintype "passive"))
      (node (ref "C49") (pin "2") (pinfunction "2_2") (pintype "passive"))
      (node (ref "C50") (pin "2") (pinfunction "2_2") (pintype "passive"))
      (node (ref "C51") (pin "2") (pinfunction "2_2") (pintype "passive"))
      (node (ref "C97") (pin "2") (pinfunction "2_2") (pintype "passive"))
      (node (ref "DEMUX1") (pin "12") (pinfunction "GND_12") (pintype "passive"))
      (node (ref "DEMUX1") (pin "15") (pinfunction "~{EN}_15") (pintype "passive"))
      (node (ref "MCU") (pin "58") (pinfunction "AVSS_58") (pintype "bidirectional"))
      (node (ref "MCU") (pin "61") (pinfunction "AVSS_61") (pintype "bidirectional"))
      (node (ref "R11") (pin "1") (pinfunction "1_1") (pintype "passive"))
      (node (ref "R34") (pin "1") (pinfunction "1_1") (pintype "passive"))
      (node (ref "R35") (pin "1") (pinfunction "1_1") (pintype "passive"))
      (node (ref "R36") (pin "1") (pinfunction "1_1") (pintype "passive"))
      (node (ref "R37") (pin "1") (pinfunction "1_1") (pintype "passive"))
      (node (ref "R38") (pin "1") (pinfunction "1_1") (pintype "passive"))
      (node (ref "R39") (pin "1") (pinfunction "1_1") (pintype "passive"))
      (node (ref "R42") (pin "1") (pinfunction "1_1") (pintype "passive"))
      (node (ref "R43") (pin "1") (pinfunction "1_1") (pintype "passive"))
      (node (ref "R44") (pin "1") (pinfunction "1_1") (pintype "passive"))
    )
    (net (code "12") (name "AVCC") (class "Default")
      (node (ref "C100") (pin "1") (pinfunction "1_1") (pintype "passive"))
      (node (ref "C122") (pin "1") (pinfunction "1_1") (pintype "passive"))
      (node (ref "C134") (pin "1") (pinfunction "1_1") (pintype "passive"))
      (node (ref "C135") (pin "1") (pinfunction "1_1") (pintype "passive"))
      (node (ref "C136") (pin "1") (pinfunction "1_1") (pintype "passive"))
      (node (ref "C30") (pin "1") (pinfunction "1_1") (pintype "passive"))
      (node (ref "C31") (pin "1") (pinfunction "1_1") (pintype "passive"))
      (node (ref "C32") (pin "1") (pinfunction "1_1") (pintype "passive"))
      (node (ref "C33") (pin "1") (pinfunction "1_1") (pintype "passive"))
      (node (ref "C34") (pin "1") (pinfunction "1_1") (pintype "passive"))
      (node (ref "C47") (pin "1") (pinfunction "1_1") (pintype "passive"))
      (node (ref "C48") (pin "1") (pinfunction "1_1") (pintype "passive"))
      (node (ref "C49") (pin "1") (pinfunction "1_1") (pintype "passive"))
      (node (ref "C50") (pin "1") (pinfunction "1_1") (pintype "passive"))
      (node (ref "C51") (pin "1") (pinfunction "1_1") (pintype "passive"))
      (node (ref "C97") (pin "1") (pinfunction "1_1") (pintype "passive"))
      (node (ref "DEMUX1") (pin "24") (pinfunction "VCC_24") (pintype "passive"))
      (node (ref "FLEX1") (pin "+") (pinfunction "+_+") (pintype "passive"))
      (node (ref "FLEX100") (pin "+") (pinfunction "+_+") (pintype "passive"))
      (node (ref "FLEX2") (pin "+") (pinfunction "+_+") (pintype "passive"))
      (node (ref "FLEX3") (pin "+") (pinfunction "+_+") (pintype "passive"))
      (node (ref "FLEX4") (pin "+") (pinfunction "+_+") (pintype "passive"))
      (node (ref "FLEX5") (pin "+") (pinfunction "+_+") (pintype "passive"))
      (node (ref "FLEX6") (pin "+") (pinfunction "+_+") (pintype "passive"))
      (node (ref "FLEX7") (pin "+") (pinfunction "+_+") (pintype "passive"))
      (node (ref "FLEX8") (pin "+") (pinfunction "+_+") (pintype "passive"))
      (node (ref "FLEX9") (pin "+") (pinfunction "+_+") (pintype "passive"))
      (node (ref "L3") (pin "2") (pinfunction "2_2") (pintype "passive"))
      (node (ref "MCU") (pin "59") (pinfunction "EVDD_59") (pintype "bidirectional"))
      (node (ref "MCU") (pin "62") (pinfunction "AREF_62") (pintype "bidirectional"))
    )
    (net (code "13") (name "C8") (class "Default")
      (node (ref "DEMUX1") (pin "23") (pinfunction "C8_23") (pintype "passive"))
    )
    (net (code "14") (name "C9") (class "Default")
      (node (ref "DEMUX1") (pin "22") (pinfunction "C9_22") (pintype "passive"))
    )
    (net (code "15") (name "C10") (class "Default")
      (node (ref "DEMUX1") (pin "21") (pinfunction "C10_21") (pintype "passive"))
    )
    (net (code "16") (name "C11") (class "Default")
      (node (ref "DEMUX1") (pin "20") (pinfunction "C11_20") (pintype "passive"))
    )
    (net (code "17") (name "C12") (class "Default")
      (node (ref "DEMUX1") (pin "19") (pinfunction "C12_19") (pintype "passive"))
    )
    (net (code "18") (name "C13") (class "Default")
      (node (ref "DEMUX1") (pin "18") (pinfunction "C13_18") (pintype "passive"))
    )
    (net (code "19") (name "GND") (class "Default")
      (node (ref "AVR_ISP") (pin "6") (pinfunction "6_6") (pintype "passive"))
      (node (ref "B2") (pin "5") (pinfunction "GND_5") (pintype "bidirectional"))
      (node (ref "BATT2") (pin "-") (pinfunction "N_-") (pintype "bidirectional"))
      (node (ref "C106") (pin "2") (pinfunction "2_2") (pintype "passive"))
      (node (ref "C107") (pin "2") (pinfunction "2_2") (pintype "passive"))
      (node (ref "C108") (pin "2") (pinfunction "2_2") (pintype "passive"))
      (node (ref "C109") (pin "2") (pinfunction "2_2") (pintype "passive"))
      (node (ref "C110") (pin "2") (pinfunction "2_2") (pintype "passive"))
      (node (ref "C111") (pin "2") (pinfunction "2_2") (pintype "passive"))
      (node (ref "C112") (pin "2") (pinfunction "2_2") (pintype "passive"))
      (node (ref "C113") (pin "2") (pinfunction "2_2") (pintype "passive"))
      (node (ref "C114") (pin "2") (pinfunction "2_2") (pintype "passive"))
      (node (ref "C115") (pin "2") (pinfunction "2_2") (pintype "passive"))
      (node (ref "C116") (pin "2") (pinfunction "2_2") (pintype "passive"))
      (node (ref "C118") (pin "2") (pinfunction "2_2") (pintype "passive"))
      (node (ref "C119") (pin "2") (pinfunction "2_2") (pintype "passive"))
      (node (ref "C12") (pin "2") (pinfunction "2_2") (pintype "passive"))
      (node (ref "C120") (pin "2") (pinfunction "2_2") (pintype "passive"))
      (node (ref "C123") (pin "2") (pinfunction "2_2") (pintype "passive"))
      (node (ref "C124") (pin "2") (pinfunction "2_2") (pintype "passive"))
      (node (ref "C126") (pin "2") (pinfunction "2_2") (pintype "passive"))
      (node (ref "C127") (pin "2") (pinfunction "2_2") (pintype "passive"))
      (node (ref "C132") (pin "2") (pinfunction "2_2") (pintype "passive"))
      (node (ref "C16") (pin "2") (pinfunction "2_2") (pintype "passive"))
      (node (ref "C2") (pin "2") (pinfunction "2_2") (pintype "passive"))
      (node (ref "C20") (pin "2") (pinfunction "2_2") (pintype "passive"))
      (node (ref "C25") (pin "2") (pinfunction "2_2") (pintype "passive"))
      (node (ref "C37") (pin "2") (pinfunction "2_2") (pintype "passive"))
      (node (ref "C38") (pin "2") (pinfunction "2_2") (pintype "passive"))
      (node (ref "C44") (pin "2") (pinfunction "2_2") (pintype "passive"))
      (node (ref "C45") (pin "2") (pinfunction "2_2") (pintype "passive"))
      (node (ref "C46") (pin "2") (pinfunction "2_2") (pintype "passive"))
      (node (ref "C8") (pin "2") (pinfunction "2_2") (pintype "passive"))
      (node (ref "C98") (pin "2") (pinfunction "2_2") (pintype "passive"))
      (node (ref "C99") (pin "2") (pinfunction "2_2") (pintype "passive"))
      (node (ref "JP2") (pin "GND") (pinfunction "6_GND") (pintype "passive"))
      (node (ref "L4") (pin "1") (pinfunction "1_1") (pintype "passive"))
      (node (ref "MCU") (pin "10") (pinfunction "AVSS_RFN_10") (pintype "bidirectional"))
      (node (ref "MCU") (pin "11") (pinfunction "TST_11") (pintype "bidirectional"))
      (node (ref "MCU") (pin "20") (pinfunction "DVSS_20") (pintype "bidirectional"))
      (node (ref "MCU") (pin "24") (pinfunction "DVSS_24") (pintype "bidirectional"))
      (node (ref "MCU") (pin "33") (pinfunction "CLKI_33") (pintype "bidirectional"))
      (node (ref "MCU") (pin "35") (pinfunction "DVSS_35") (pintype "bidirectional"))
      (node (ref "MCU") (pin "45") (pinfunction "DVSS_45") (pintype "bidirectional"))
      (node (ref "MCU") (pin "55") (pinfunction "DVSS_55") (pintype "bidirectional"))
      (node (ref "MCU") (pin "7") (pinfunction "AVSS_RFP_7") (pintype "bidirectional"))
      (node (ref "NOISE_BR") (pin "P$2") (pinfunction "P$2_P$2") (pintype "bidirectional"))
      (node (ref "PWM_DRIVER1") (pin "1") (pinfunction "A0_1") (pintype "passive"))
      (node (ref "PWM_DRIVER1") (pin "14") (pinfunction "GND_14") (pintype "passive"))
      (node (ref "PWM_DRIVER1") (pin "2") (pinfunction "A1_2") (pintype "passive"))
      (node (ref "PWM_DRIVER1") (pin "23") (pinfunction "~{OE}_23") (pintype "passive"))
      (node (ref "PWM_DRIVER1") (pin "24") (pinfunction "A5_24") (pintype "passive"))
      (node (ref "PWM_DRIVER1") (pin "25") (pinfunction "EXTCLK_25") (pintype "passive"))
      (node (ref "PWM_DRIVER1") (pin "3") (pinfunction "A2_3") (pintype "passive"))
      (node (ref "PWM_DRIVER1") (pin "4") (pinfunction "A3_4") (pintype "passive"))
      (node (ref "PWM_DRIVER1") (pin "5") (pinfunction "A4_5") (pintype "passive"))
      (node (ref "R14") (pin "1") (pinfunction "1_1") (pintype "passive"))
      (node (ref "R16") (pin "1") (pinfunction "1_1") (pintype "passive"))
      (node (ref "R18") (pin "1") (pinfunction "1_1") (pintype "passive"))
      (node (ref "R20") (pin "1") (pinfunction "1_1") (pintype "passive"))
      (node (ref "R22") (pin "1") (pinfunction "1_1") (pintype "passive"))
      (node (ref "R24") (pin "1") (pinfunction "1_1") (pintype "passive"))
      (node (ref "R26") (pin "1") (pinfunction "1_1") (pintype "passive"))
      (node (ref "R28") (pin "1") (pinfunction "1_1") (pintype "passive"))
      (node (ref "R30") (pin "1") (pinfunction "1_1") (pintype "passive"))
      (node (ref "R32") (pin "1") (pinfunction "1_1") (pintype "passive"))
      (node (ref "R47") (pin "1") (pinfunction "1_1") (pintype "passive"))
      (node (ref "R48") (pin "1") (pinfunction "1_1") (pintype "passive"))
      (node (ref "R49") (pin "1") (pinfunction "1_1") (pintype "passive"))
      (node (ref "VREG1") (pin "1") (pinfunction "GND_1") (pintype "bidirectional"))
      (node (ref "VREG1") (pin "2") (pinfunction "~{EN}_2") (pintype "bidirectional"))
    )
    (net (code "20") (name "MISO") (class "Default")
      (node (ref "AVR_ISP") (pin "1") (pinfunction "1_1") (pintype "passive"))
      (node (ref "MCU") (pin "39") (pinfunction "(PDO/PCINT3/MISO/D12)PB3_39") (pintype "bidirectional"))
    )
    (net (code "21") (name "MOSI") (class "Default")
      (node (ref "AVR_ISP") (pin "4") (pinfunction "4_4") (pintype "passive"))
      (node (ref "MCU") (pin "38") (pinfunction "(PDI/PCINT2/MOSI/D11)PB2_38") (pintype "bidirectional"))
    )
    (net (code "22") (name "NGND") (class "Default")
      (node (ref "C10") (pin "2") (pinfunction "2_2") (pintype "passive"))
      (node (ref "C13") (pin "2") (pinfunction "2_2") (pintype "passive"))
      (node (ref "C14") (pin "2") (pinfunction "2_2") (pintype "passive"))
      (node (ref "C17") (pin "2") (pinfunction "2_2") (pintype "passive"))
      (node (ref "C18") (pin "2") (pinfunction "2_2") (pintype "passive"))
      (node (ref "C21") (pin "2") (pinfunction "2_2") (pintype "passive"))
      (node (ref "C22") (pin "2") (pinfunction "2_2") (pintype "passive"))
      (node (ref "C26") (pin "2") (pinfunction "2_2") (pintype "passive"))
      (node (ref "C27") (pin "2") (pinfunction "2_2") (pintype "passive"))
      (node (ref "C36") (pin "2") (pinfunction "2_2") (pintype "passive"))
      (node (ref "C39") (pin "2") (pinfunction "2_2") (pintype "passive"))
      (node (ref "C40") (pin "2") (pinfunction "2_2") (pintype "passive"))
      (node (ref "C41") (pin "2") (pinfunction "2_2") (pintype "passive"))
      (node (ref "C42") (pin "2") (pinfunction "2_2") (pintype "passive"))
      (node (ref "C43") (pin "2") (pinfunction "2_2") (pintype "passive"))
      (node (ref "C9") (pin "2") (pinfunction "2_2") (pintype "passive"))
      (node (ref "HBRIDGE1") (pin "4") (pinfunction "GND_4") (pintype "passive"))
      (node (ref "HBRIDGE1") (pin "GND") (pinfunction "GND_GND") (pintype "passive"))
      (node (ref "HBRIDGE1") (pin "P$1") (pinfunction "GND_P$1") (pintype "passive"))
      (node (ref "HBRIDGE1") (pin "P$2") (pinfunction "GND_P$2") (pintype "passive"))
      (node (ref "HBRIDGE2") (pin "4") (pinfunction "GND_4") (pintype "passive"))
      (node (ref "HBRIDGE2") (pin "GND") (pinfunction "GND_GND") (pintype "passive"))
      (node (ref "HBRIDGE2") (pin "P$1") (pinfunction "GND_P$1") (pintype "passive"))
      (node (ref "HBRIDGE2") (pin "P$2") (pinfunction "GND_P$2") (pintype "passive"))
      (node (ref "HBRIDGE3") (pin "4") (pinfunction "GND_4") (pintype "passive"))
      (node (ref "HBRIDGE3") (pin "GND") (pinfunction "GND_GND") (pintype "passive"))
      (node (ref "HBRIDGE3") (pin "P$1") (pinfunction "GND_P$1") (pintype "passive"))
      (node (ref "HBRIDGE3") (pin "P$2") (pinfunction "GND_P$2") (pintype "passive"))
      (node (ref "HBRIDGE4") (pin "4") (pinfunction "GND_4") (pintype "passive"))
      (node (ref "HBRIDGE4") (pin "GND") (pinfunction "GND_GND") (pintype "passive"))
      (node (ref "HBRIDGE4") (pin "P$1") (pinfunction "GND_P$1") (pintype "passive"))
      (node (ref "HBRIDGE4") (pin "P$2") (pinfunction "GND_P$2") (pintype "passive"))
      (node (ref "HBRIDGE5") (pin "4") (pinfunction "GND_4") (pintype "passive"))
      (node (ref "HBRIDGE5") (pin "GND") (pinfunction "GND_GND") (pintype "passive"))
      (node (ref "HBRIDGE5") (pin "P$1") (pinfunction "GND_P$1") (pintype "passive"))
      (node (ref "HBRIDGE5") (pin "P$2") (pinfunction "GND_P$2") (pintype "passive"))
      (node (ref "NOISE_BR") (pin "P$1") (pinfunction "P$1_P$1") (pintype "bidirectional"))
      (node (ref "Q1") (pin "2") (pinfunction "S_2") (pintype "passive"))
      (node (ref "Q2") (pin "2") (pinfunction "S_2") (pintype "passive"))
      (node (ref "Q3") (pin "2") (pinfunction "S_2") (pintype "passive"))
      (node (ref "Q4") (pin "2") (pinfunction "S_2") (pintype "passive"))
      (node (ref "Q5") (pin "2") (pinfunction "S_2") (pintype "passive"))
      (node (ref "Q6") (pin "2") (pinfunction "S_2") (pintype "passive"))
      (node (ref "R1") (pin "1") (pinfunction "1_1") (pintype "passive"))
      (node (ref "R12") (pin "1") (pinfunction "1_1") (pintype "passive"))
      (node (ref "R2") (pin "1") (pinfunction "1_1") (pintype "passive"))
      (node (ref "R3") (pin "1") (pinfunction "1_1") (pintype "passive"))
      (node (ref "R4") (pin "1") (pinfunction "1_1") (pintype "passive"))
      (node (ref "R5") (pin "1") (pinfunction "1_1") (pintype "passive"))
      (node (ref "VREG6") (pin "2") (pinfunction "GND_2") (pintype "bidirectional"))
      (node (ref "VREG6") (pin "TAB") (pinfunction "GND_TAB") (pintype "bidirectional"))
      (node (ref "VREG7") (pin "3") (pinfunction "GND_3") (pintype "bidirectional"))
      (node (ref "VREG7") (pin "TAB") (pinfunction "GND_TAB") (pintype "bidirectional"))
    )
    (net (code "23") (name "Net-(A6-SIGNAL)") (class "Default")
      (node (ref "A6") (pin "FEED") (pinfunction "SIGNAL_FEED") (pintype "bidirectional"))
      (node (ref "B2") (pin "1") (pinfunction "IN_1") (pintype "bidirectional"))
      (node (ref "C115") (pin "1") (pinfunction "1_1") (pintype "passive"))
    )
    (net (code "24") (name "Net-(ANALOG_BR-PadP$1)") (class "Default")
      (node (ref "ANALOG_BR") (pin "P$1") (pinfunction "P$1_P$1") (pintype "bidirectional"))
      (node (ref "L4") (pin "2") (pinfunction "2_2") (pintype "passive"))
    )
    (net (code "25") (name "Net-(B2-GND-Pad2)") (class "Default")
      (node (ref "B2") (pin "2") (pinfunction "GND_2") (pintype "bidirectional"))
      (node (ref "C114") (pin "1") (pinfunction "1_1") (pintype "passive"))
    )
    (net (code "26") (name "Net-(B2-OUT1)") (class "Default")
      (node (ref "B2") (pin "4") (pinfunction "OUT1_4") (pintype "bidirectional"))
      (node (ref "MCU") (pin "8") (pinfunction "RFP_8") (pintype "bidirectional"))
    )
    (net (code "27") (name "Net-(B2-OUT2)") (class "Default")
      (node (ref "B2") (pin "3") (pinfunction "OUT2_3") (pintype "bidirectional"))
      (node (ref "MCU") (pin "9") (pinfunction "RFN_9") (pintype "bidirectional"))
    )
    (net (code "28") (name "Net-(BATT2-P)") (class "Default")
      (node (ref "BATT2") (pin "+") (pinfunction "P_+") (pintype "bidirectional"))
      (node (ref "SW1") (pin "P") (pinfunction "1_P") (pintype "passive"))
    )
    (net (code "29") (name "Net-(C132-Pad1)") (class "Default")
      (node (ref "C132") (pin "1") (pinfunction "1_1") (pintype "passive"))
      (node (ref "MCU") (pin "21") (pinfunction "DVDD_21") (pintype "bidirectional"))
      (node (ref "MCU") (pin "22") (pinfunction "DVDD_22") (pintype "bidirectional"))
    )
    (net (code "30") (name "Net-(HBRIDGE1-IN1)") (class "Default")
      (node (ref "HBRIDGE1") (pin "6") (pinfunction "IN1_6") (pintype "passive"))
      (node (ref "R28") (pin "2") (pinfunction "2_2") (pintype "passive"))
      (node (ref "R29") (pin "2") (pinfunction "2_2") (pintype "passive"))
    )
    (net (code "31") (name "Net-(HBRIDGE1-IN2)") (class "Default")
      (node (ref "HBRIDGE1") (pin "5") (pinfunction "IN2_5") (pintype "passive"))
      (node (ref "R26") (pin "2") (pinfunction "2_2") (pintype "passive"))
      (node (ref "R27") (pin "2") (pinfunction "2_2") (pintype "passive"))
    )
    (net (code "32") (name "Net-(HBRIDGE1-OUT1)") (class "Default")
      (node (ref "HBRIDGE1") (pin "2") (pinfunction "OUT1_2") (pintype "passive"))
      (node (ref "TEC1") (pin "COLD") (pinfunction "COLD_COLD") (pintype "passive"))
    )
    (net (code "33") (name "Net-(HBRIDGE1-OUT2)") (class "Default")
      (node (ref "HBRIDGE1") (pin "3") (pinfunction "OUT2_3") (pintype "passive"))
      (node (ref "TEC1") (pin "HOT") (pinfunction "HOT_HOT") (pintype "passive"))
    )
    (net (code "34") (name "Net-(HBRIDGE2-IN1)") (class "Default")
      (node (ref "HBRIDGE2") (pin "6") (pinfunction "IN1_6") (pintype "passive"))
      (node (ref "R24") (pin "2") (pinfunction "2_2") (pintype "passive"))
      (node (ref "R25") (pin "2") (pinfunction "2_2") (pintype "passive"))
    )
    (net (code "35") (name "Net-(HBRIDGE2-IN2)") (class "Default")
      (node (ref "HBRIDGE2") (pin "5") (pinfunction "IN2_5") (pintype "passive"))
      (node (ref "R22") (pin "2") (pinfunction "2_2") (pintype "passive"))
      (node (ref "R23") (pin "2") (pinfunction "2_2") (pintype "passive"))
    )
    (net (code "36") (name "Net-(HBRIDGE2-OUT1)") (class "Default")
      (node (ref "HBRIDGE2") (pin "2") (pinfunction "OUT1_2") (pintype "passive"))
      (node (ref "TEC2") (pin "COLD") (pinfunction "COLD_COLD") (pintype "passive"))
    )
    (net (code "37") (name "Net-(HBRIDGE2-OUT2)") (class "Default")
      (node (ref "HBRIDGE2") (pin "3") (pinfunction "OUT2_3") (pintype "passive"))
      (node (ref "TEC2") (pin "HOT") (pinfunction "HOT_HOT") (pintype "passive"))
    )
    (net (code "38") (name "Net-(HBRIDGE3-IN1)") (class "Default")
      (node (ref "HBRIDGE3") (pin "6") (pinfunction "IN1_6") (pintype "passive"))
      (node (ref "R20") (pin "2") (pinfunction "2_2") (pintype "passive"))
      (node (ref "R21") (pin "2") (pinfunction "2_2") (pintype "passive"))
    )
    (net (code "39") (name "Net-(HBRIDGE3-IN2)") (class "Default")
      (node (ref "HBRIDGE3") (pin "5") (pinfunction "IN2_5") (pintype "passive"))
      (node (ref "R18") (pin "2") (pinfunction "2_2") (pintype "passive"))
      (node (ref "R19") (pin "2") (pinfunction "2_2") (pintype "passive"))
    )
    (net (code "40") (name "Net-(HBRIDGE3-OUT1)") (class "Default")
      (node (ref "HBRIDGE3") (pin "2") (pinfunction "OUT1_2") (pintype "passive"))
      (node (ref "TEC3") (pin "COLD") (pinfunction "COLD_COLD") (pintype "passive"))
    )
    (net (code "41") (name "Net-(HBRIDGE3-OUT2)") (class "Default")
      (node (ref "HBRIDGE3") (pin "3") (pinfunction "OUT2_3") (pintype "passive"))
      (node (ref "TEC3") (pin "HOT") (pinfunction "HOT_HOT") (pintype "passive"))
    )
    (net (code "42") (name "Net-(HBRIDGE4-IN1)") (class "Default")
      (node (ref "HBRIDGE4") (pin "6") (pinfunction "IN1_6") (pintype "passive"))
      (node (ref "R16") (pin "2") (pinfunction "2_2") (pintype "passive"))
      (node (ref "R17") (pin "2") (pinfunction "2_2") (pintype "passive"))
    )
    (net (code "43") (name "Net-(HBRIDGE4-IN2)") (class "Default")
      (node (ref "HBRIDGE4") (pin "5") (pinfunction "IN2_5") (pintype "passive"))
      (node (ref "R14") (pin "2") (pinfunction "2_2") (pintype "passive"))
      (node (ref "R15") (pin "2") (pinfunction "2_2") (pintype "passive"))
    )
    (net (code "44") (name "Net-(HBRIDGE4-OUT1)") (class "Default")
      (node (ref "HBRIDGE4") (pin "2") (pinfunction "OUT1_2") (pintype "passive"))
      (node (ref "TEC4") (pin "COLD") (pinfunction "COLD_COLD") (pintype "passive"))
    )
    (net (code "45") (name "Net-(HBRIDGE4-OUT2)") (class "Default")
      (node (ref "HBRIDGE4") (pin "3") (pinfunction "OUT2_3") (pintype "passive"))
      (node (ref "TEC4") (pin "HOT") (pinfunction "HOT_HOT") (pintype "passive"))
    )
    (net (code "46") (name "Net-(HBRIDGE5-IN1)") (class "Default")
      (node (ref "HBRIDGE5") (pin "6") (pinfunction "IN1_6") (pintype "passive"))
      (node (ref "R32") (pin "2") (pinfunction "2_2") (pintype "passive"))
      (node (ref "R33") (pin "2") (pinfunction "2_2") (pintype "passive"))
    )
    (net (code "47") (name "Net-(HBRIDGE5-IN2)") (class "Default")
      (node (ref "HBRIDGE5") (pin "5") (pinfunction "IN2_5") (pintype "passive"))
      (node (ref "R30") (pin "2") (pinfunction "2_2") (pintype "passive"))
      (node (ref "R31") (pin "2") (pinfunction "2_2") (pintype "passive"))
    )
    (net (code "48") (name "Net-(HBRIDGE5-OUT1)") (class "Default")
      (node (ref "HBRIDGE5") (pin "2") (pinfunction "OUT1_2") (pintype "passive"))
      (node (ref "TEC5") (pin "COLD") (pinfunction "COLD_COLD") (pintype "passive"))
    )
    (net (code "49") (name "Net-(HBRIDGE5-OUT2)") (class "Default")
      (node (ref "HBRIDGE5") (pin "3") (pinfunction "OUT2_3") (pintype "passive"))
      (node (ref "TEC5") (pin "HOT") (pinfunction "HOT_HOT") (pintype "passive"))
    )
    (net (code "50") (name "Net-(JP2-2)") (class "Default")
      (node (ref "C117") (pin "1") (pinfunction "1_1") (pintype "passive"))
      (node (ref "JP2") (pin "DTR") (pinfunction "2_DTR") (pintype "passive"))
    )
    (net (code "51") (name "Net-(LED1-PadK)") (class "Default")
      (node (ref "LED1") (pin "K") (pinfunction "K_K") (pintype "passive"))
      (node (ref "R49") (pin "2") (pinfunction "2_2") (pintype "passive"))
    )
    (net (code "52") (name "Net-(LED2-PadK)") (class "Default")
      (node (ref "LED2") (pin "K") (pinfunction "K_K") (pintype "passive"))
      (node (ref "R48") (pin "2") (pinfunction "2_2") (pintype "passive"))
    )
    (net (code "53") (name "Net-(LED3-PadK)") (class "Default")
      (node (ref "LED3") (pin "K") (pinfunction "K_K") (pintype "passive"))
      (node (ref "R47") (pin "2") (pinfunction "2_2") (pintype "passive"))
    )
    (net (code "54") (name "Net-(MCU-AVDD)") (class "Default")
      (node (ref "C110") (pin "1") (pinfunction "1_1") (pintype "passive"))
      (node (ref "MCU") (pin "60") (pinfunction "AVDD_60") (pintype "bidirectional"))
    )
    (net (code "55") (name "Net-(MCU-XTAL1)") (class "Default")
      (node (ref "C113") (pin "1") (pinfunction "1_1") (pintype "passive"))
      (node (ref "MCU") (pin "57") (pinfunction "XTAL1_57") (pintype "bidirectional"))
      (node (ref "Y2") (pin "3") (pinfunction "2_3") (pintype "passive"))
    )
    (net (code "56") (name "Net-(MCU-XTAL2)") (class "Default")
      (node (ref "C112") (pin "1") (pinfunction "1_1") (pintype "passive"))
      (node (ref "MCU") (pin "56") (pinfunction "XTAL2_56") (pintype "bidirectional"))
      (node (ref "Y2") (pin "1") (pinfunction "1_1") (pintype "passive"))
    )
    (net (code "57") (name "Net-(Q1-D)") (class "Default")
      (node (ref "C3") (pin "2") (pinfunction "2_2") (pintype "passive"))
      (node (ref "D1") (pin "A") (pinfunction "A_A") (pintype "passive"))
      (node (ref "Q1") (pin "3") (pinfunction "D_3") (pintype "passive"))
      (node (ref "VIBE1") (pin "2") (pinfunction "-_2") (pintype "passive"))
    )
    (net (code "58") (name "Net-(Q1-G)") (class "Default")
      (node (ref "Q1") (pin "1") (pinfunction "G_1") (pintype "passive"))
      (node (ref "R1") (pin "2") (pinfunction "2_2") (pintype "passive"))
      (node (ref "R6") (pin "2") (pinfunction "2_2") (pintype "passive"))
    )
    (net (code "59") (name "Net-(Q2-D)") (class "Default")
      (node (ref "C4") (pin "2") (pinfunction "2_2") (pintype "passive"))
      (node (ref "D2") (pin "A") (pinfunction "A_A") (pintype "passive"))
      (node (ref "Q2") (pin "3") (pinfunction "D_3") (pintype "passive"))
      (node (ref "VIBE2") (pin "2") (pinfunction "-_2") (pintype "passive"))
    )
    (net (code "60") (name "Net-(Q2-G)") (class "Default")
      (node (ref "Q2") (pin "1") (pinfunction "G_1") (pintype "passive"))
      (node (ref "R2") (pin "2") (pinfunction "2_2") (pintype "passive"))
      (node (ref "R7") (pin "2") (pinfunction "2_2") (pintype "passive"))
    )
    (net (code "61") (name "Net-(Q3-D)") (class "Default")
      (node (ref "C5") (pin "2") (pinfunction "2_2") (pintype "passive"))
      (node (ref "D3") (pin "A") (pinfunction "A_A") (pintype "passive"))
      (node (ref "Q3") (pin "3") (pinfunction "D_3") (pintype "passive"))
      (node (ref "VIBE3") (pin "2") (pinfunction "-_2") (pintype "passive"))
    )
    (net (code "62") (name "Net-(Q3-G)") (class "Default")
      (node (ref "Q3") (pin "1") (pinfunction "G_1") (pintype "passive"))
      (node (ref "R3") (pin "2") (pinfunction "2_2") (pintype "passive"))
      (node (ref "R8") (pin "2") (pinfunction "2_2") (pintype "passive"))
    )
    (net (code "63") (name "Net-(Q4-D)") (class "Default")
      (node (ref "C6") (pin "2") (pinfunction "2_2") (pintype "passive"))
      (node (ref "D4") (pin "A") (pinfunction "A_A") (pintype "passive"))
      (node (ref "Q4") (pin "3") (pinfunction "D_3") (pintype "passive"))
      (node (ref "VIBE4") (pin "2") (pinfunction "-_2") (pintype "passive"))
    )
    (net (code "64") (name "Net-(Q4-G)") (class "Default")
      (node (ref "Q4") (pin "1") (pinfunction "G_1") (pintype "passive"))
      (node (ref "R4") (pin "2") (pinfunction "2_2") (pintype "passive"))
      (node (ref "R9") (pin "2") (pinfunction "2_2") (pintype "passive"))
    )
    (net (code "65") (name "Net-(Q5-D)") (class "Default")
      (node (ref "C7") (pin "2") (pinfunction "2_2") (pintype "passive"))
      (node (ref "D5") (pin "A") (pinfunction "A_A") (pintype "passive"))
      (node (ref "Q5") (pin "3") (pinfunction "D_3") (pintype "passive"))
      (node (ref "VIBE5") (pin "2") (pinfunction "-_2") (pintype "passive"))
    )
    (net (code "66") (name "Net-(Q5-G)") (class "Default")
      (node (ref "Q5") (pin "1") (pinfunction "G_1") (pintype "passive"))
      (node (ref "R10") (pin "2") (pinfunction "2_2") (pintype "passive"))
      (node (ref "R5") (pin "2") (pinfunction "2_2") (pintype "passive"))
    )
    (net (code "67") (name "Net-(Q6-D)") (class "Default")
      (node (ref "C1") (pin "2") (pinfunction "2_2") (pintype "passive"))
      (node (ref "D12") (pin "A") (pinfunction "A_A") (pintype "passive"))
      (node (ref "Q6") (pin "3") (pinfunction "D_3") (pintype "passive"))
      (node (ref "VIBE6") (pin "2") (pinfunction "-_2") (pintype "passive"))
    )
    (net (code "68") (name "Net-(Q6-G)") (class "Default")
      (node (ref "Q6") (pin "1") (pinfunction "G_1") (pintype "passive"))
      (node (ref "R12") (pin "2") (pinfunction "2_2") (pintype "passive"))
      (node (ref "R13") (pin "2") (pinfunction "2_2") (pintype "passive"))
    )
    (net (code "69") (name "PB4") (class "Default")
      (node (ref "MCU") (pin "40") (pinfunction "(PCINT4/OC2A/D9-PWM9)PB4_40") (pintype "bidirectional"))
    )
    (net (code "70") (name "PB5") (class "Default")
      (node (ref "MCU") (pin "41") (pinfunction "(PCINT5/OC1A/D8-PWM8)PB5_41") (pintype "bidirectional"))
    )
    (net (code "71") (name "PB6") (class "Default")
      (node (ref "LED2") (pin "A") (pinfunction "A_A") (pintype "passive"))
      (node (ref "MCU") (pin "42") (pinfunction "(PCINT6/OC1B/D34-PWM34)PB6_42") (pintype "bidirectional"))
    )
    (net (code "72") (name "PB7") (class "Default")
      (node (ref "LED1") (pin "A") (pinfunction "A_A") (pintype "passive"))
      (node (ref "MCU") (pin "43") (pinfunction "(PCINT7/OC0A/OC1C/D35-PWM35)PB7_43") (pintype "bidirectional"))
    )
    (net (code "73") (name "PD4") (class "Default")
      (node (ref "DEMUX1") (pin "13") (pinfunction "S3_13") (pintype "passive"))
      (node (ref "MCU") (pin "29") (pinfunction "(ICP1/D22)PD4_29") (pintype "bidirectional"))
    )
    (net (code "74") (name "PD5") (class "Default")
      (node (ref "DEMUX1") (pin "14") (pinfunction "S2_14") (pintype "passive"))
      (node (ref "MCU") (pin "30") (pinfunction "(XCK1/D23)PD5_30") (pintype "bidirectional"))
    )
    (net (code "75") (name "PD6") (class "Default")
      (node (ref "DEMUX1") (pin "11") (pinfunction "S1_11") (pintype "passive"))
      (node (ref "MCU") (pin "31") (pinfunction "(T1/D24)PD6_31") (pintype "bidirectional"))
    )
    (net (code "76") (name "PD7") (class "Default")
      (node (ref "DEMUX1") (pin "10") (pinfunction "S0_10") (pintype "passive"))
      (node (ref "MCU") (pin "32") (pinfunction "(T0/D25)PD7_32") (pintype "bidirectional"))
    )
    (net (code "77") (name "PE2") (class "Default")
      (node (ref "MCU") (pin "48") (pinfunction "(XCK0/AIN0/D2)PE2_48") (pintype "bidirectional"))
    )
    (net (code "78") (name "PE3") (class "Default")
      (node (ref "MCU") (pin "49") (pinfunction "(AIN1/OC3A/D3-PWM3)PE3_49") (pintype "bidirectional"))
    )
    (net (code "79") (name "PE4") (class "Default")
      (node (ref "MCU") (pin "50") (pinfunction "(INT4/OC3B/D4-PWM4)PE4_50") (pintype "bidirectional"))
    )
    (net (code "80") (name "PE5") (class "Default")
      (node (ref "MCU") (pin "51") (pinfunction "(INT5/OC3C/D5-PWM5)PE5_51") (pintype "bidirectional"))
    )
    (net (code "81") (name "PE6") (class "Default")
      (node (ref "MCU") (pin "52") (pinfunction "(T3/INT6/D6)PE6_52") (pintype "bidirectional"))
    )
    (net (code "82") (name "PE7") (class "Default")
      (node (ref "MCU") (pin "53") (pinfunction "(ICP3/INT7/CLKO/D7)PE7_53") (pintype "bidirectional"))
    )
    (net (code "83") (name "PG0") (class "Default")
      (node (ref "MCU") (pin "14") (pinfunction "(DIG3/D16)PG0_14") (pintype "bidirectional"))
    )
    (net (code "84") (name "PG1") (class "Default")
      (node (ref "MCU") (pin "15") (pinfunction "(DIG1/D17)PG1_15") (pintype "bidirectional"))
    )
    (net (code "85") (name "PG2") (class "Default")
      (node (ref "MCU") (pin "16") (pinfunction "(AMR/D18)PG2_16") (pintype "bidirectional"))
    )
    (net (code "86") (name "PG3") (class "Default")
      (node (ref "MCU") (pin "17") (pinfunction "(TOSC2)PG3_17") (pintype "bidirectional"))
    )
    (net (code "87") (name "PG4") (class "Default")
      (node (ref "MCU") (pin "18") (pinfunction "(TOSC1)PG4_18") (pintype "bidirectional"))
    )
    (net (code "88") (name "PG5") (class "Default")
      (node (ref "MCU") (pin "19") (pinfunction "(OC0B/D19-PWM19)PG5_19") (pintype "bidirectional"))
    )
    (net (code "89") (name "RESET") (class "Default")
      (node (ref "AVR_ISP") (pin "5") (pinfunction "5_5") (pintype "passive"))
      (node (ref "C117") (pin "2") (pinfunction "2_2") (pintype "passive"))
      (node (ref "D11") (pin "A") (pinfunction "A_A") (pintype "passive"))
      (node (ref "MCU") (pin "12") (pinfunction "RSTN_12") (pintype "bidirectional"))
      (node (ref "R46") (pin "1") (pinfunction "1_1") (pintype "passive"))
    )
    (net (code "90") (name "RX0") (class "Default")
      (node (ref "JP2") (pin "TXO") (pinfunction "4_TXO") (pintype "passive"))
      (node (ref "MCU") (pin "46") (pinfunction "(PCINT8/RXD0/D0)PE0_46") (pintype "bidirectional"))
    )
    (net (code "91") (name "RX1") (class "Default")
      (node (ref "MCU") (pin "27") (pinfunction "(INT2/RXD1/D20)PD2_27") (pintype "bidirectional"))
    )
    (net (code "92") (name "SCK") (class "Default")
      (node (ref "AVR_ISP") (pin "3") (pinfunction "3_3") (pintype "passive"))
      (node (ref "MCU") (pin "37") (pinfunction "(PCINT1/SCK/D13)PB1_37") (pintype "bidirectional"))
    )
    (net (code "93") (name "SCL") (class "Default")
      (node (ref "MCU") (pin "25") (pinfunction "(INT0/SCL/D15)PD0_25") (pintype "bidirectional"))
      (node (ref "PWM_DRIVER1") (pin "26") (pinfunction "SCL_26") (pintype "passive"))
      (node (ref "R40") (pin "1") (pinfunction "1_1") (pintype "passive"))
    )
    (net (code "94") (name "SDA") (class "Default")
      (node (ref "MCU") (pin "26") (pinfunction "(INT1/SDA/D14)PD1_26") (pintype "bidirectional"))
      (node (ref "PWM_DRIVER1") (pin "27") (pinfunction "SDA_27") (pintype "passive"))
      (node (ref "R41") (pin "1") (pinfunction "1_1") (pintype "passive"))
    )
    (net (code "95") (name "SSN") (class "Default")
      (node (ref "MCU") (pin "36") (pinfunction "(PCINT0/SSN/D10)PB0_36") (pintype "bidirectional"))
    )
    (net (code "96") (name "STRAIN_1") (class "Default")
      (node (ref "DEMUX1") (pin "9") (pinfunction "C0_9") (pintype "passive"))
      (node (ref "FLEX1") (pin "-") (pinfunction "-_-") (pintype "passive"))
      (node (ref "R34") (pin "2") (pinfunction "2_2") (pintype "passive"))
    )
    (net (code "97") (name "STRAIN_2") (class "Default")
      (node (ref "DEMUX1") (pin "8") (pinfunction "C1_8") (pintype "passive"))
      (node (ref "FLEX2") (pin "-") (pinfunction "-_-") (pintype "passive"))
      (node (ref "R39") (pin "2") (pinfunction "2_2") (pintype "passive"))
    )
    (net (code "98") (name "STRAIN_3") (class "Default")
      (node (ref "DEMUX1") (pin "7") (pinfunction "C2_7") (pintype "passive"))
      (node (ref "FLEX3") (pin "-") (pinfunction "-_-") (pintype "passive"))
      (node (ref "R35") (pin "2") (pinfunction "2_2") (pintype "passive"))
    )
    (net (code "99") (name "STRAIN_4") (class "Default")
      (node (ref "DEMUX1") (pin "6") (pinfunction "C3_6") (pintype "passive"))
      (node (ref "FLEX4") (pin "-") (pinfunction "-_-") (pintype "passive"))
      (node (ref "R42") (pin "2") (pinfunction "2_2") (pintype "passive"))
    )
    (net (code "100") (name "STRAIN_5") (class "Default")
      (node (ref "DEMUX1") (pin "5") (pinfunction "C4_5") (pintype "passive"))
      (node (ref "FLEX5") (pin "-") (pinfunction "-_-") (pintype "passive"))
      (node (ref "R36") (pin "2") (pinfunction "2_2") (pintype "passive"))
    )
    (net (code "101") (name "STRAIN_6") (class "Default")
      (node (ref "DEMUX1") (pin "4") (pinfunction "C5_4") (pintype "passive"))
      (node (ref "FLEX6") (pin "-") (pinfunction "-_-") (pintype "passive"))
      (node (ref "R43") (pin "2") (pinfunction "2_2") (pintype "passive"))
    )
    (net (code "102") (name "STRAIN_7") (class "Default")
      (node (ref "DEMUX1") (pin "3") (pinfunction "C6_3") (pintype "passive"))
      (node (ref "FLEX7") (pin "-") (pinfunction "-_-") (pintype "passive"))
      (node (ref "R37") (pin "2") (pinfunction "2_2") (pintype "passive"))
    )
    (net (code "103") (name "STRAIN_8") (class "Default")
      (node (ref "DEMUX1") (pin "2") (pinfunction "C7_2") (pintype "passive"))
      (node (ref "FLEX8") (pin "-") (pinfunction "-_-") (pintype "passive"))
      (node (ref "R44") (pin "2") (pinfunction "2_2") (pintype "passive"))
    )
    (net (code "104") (name "STRAIN_9") (class "Default")
      (node (ref "DEMUX1") (pin "17") (pinfunction "C14_17") (pintype "passive"))
      (node (ref "FLEX9") (pin "-") (pinfunction "-_-") (pintype "passive"))
      (node (ref "R11") (pin "2") (pinfunction "2_2") (pintype "passive"))
    )
    (net (code "105") (name "STRAIN_10") (class "Default")
      (node (ref "DEMUX1") (pin "16") (pinfunction "C15_16") (pintype "passive"))
      (node (ref "FLEX100") (pin "-") (pinfunction "-_-") (pintype "passive"))
      (node (ref "R38") (pin "2") (pinfunction "2_2") (pintype "passive"))
    )
    (net (code "106") (name "TEC_1_COLD") (class "Default")
      (node (ref "PWM_DRIVER1") (pin "12") (pinfunction "PWM6_12") (pintype "passive"))
      (node (ref "R27") (pin "1") (pinfunction "1_1") (pintype "passive"))
    )
    (net (code "107") (name "TEC_1_HOT") (class "Default")
      (node (ref "PWM_DRIVER1") (pin "13") (pinfunction "PWM7_13") (pintype "passive"))
      (node (ref "R29") (pin "1") (pinfunction "1_1") (pintype "passive"))
    )
    (net (code "108") (name "TEC_2_COLD") (class "Default")
      (node (ref "PWM_DRIVER1") (pin "21") (pinfunction "PWM14_21") (pintype "passive"))
      (node (ref "R23") (pin "1") (pinfunction "1_1") (pintype "passive"))
    )
    (net (code "109") (name "TEC_2_HOT") (class "Default")
      (node (ref "PWM_DRIVER1") (pin "22") (pinfunction "PWM15_22") (pintype "passive"))
      (node (ref "R25") (pin "1") (pinfunction "1_1") (pintype "passive"))
    )
    (net (code "110") (name "TEC_3_COLD") (class "Default")
      (node (ref "PWM_DRIVER1") (pin "19") (pinfunction "PWM12_19") (pintype "passive"))
      (node (ref "R19") (pin "1") (pinfunction "1_1") (pintype "passive"))
    )
    (net (code "111") (name "TEC_3_HOT") (class "Default")
      (node (ref "PWM_DRIVER1") (pin "20") (pinfunction "PWM13_20") (pintype "passive"))
      (node (ref "R21") (pin "1") (pinfunction "1_1") (pintype "passive"))
    )
    (net (code "112") (name "TEC_4_COLD") (class "Default")
      (node (ref "PWM_DRIVER1") (pin "17") (pinfunction "PWM10_17") (pintype "passive"))
      (node (ref "R15") (pin "1") (pinfunction "1_1") (pintype "passive"))
    )
    (net (code "113") (name "TEC_4_HOT") (class "Default")
      (node (ref "PWM_DRIVER1") (pin "18") (pinfunction "PWM11_18") (pintype "passive"))
      (node (ref "R17") (pin "1") (pinfunction "1_1") (pintype "passive"))
    )
    (net (code "114") (name "TEC_5_COLD") (class "Default")
      (node (ref "PWM_DRIVER1") (pin "15") (pinfunction "PWM8_15") (pintype "passive"))
      (node (ref "R31") (pin "1") (pinfunction "1_1") (pintype "passive"))
    )
    (net (code "115") (name "TEC_5_HOT") (class "Default")
      (node (ref "PWM_DRIVER1") (pin "16") (pinfunction "PWM9_16") (pintype "passive"))
      (node (ref "R33") (pin "1") (pinfunction "1_1") (pintype "passive"))
    )
    (net (code "116") (name "TX0") (class "Default")
      (node (ref "JP2") (pin "RXI") (pinfunction "3_RXI") (pintype "passive"))
      (node (ref "MCU") (pin "47") (pinfunction "(TXD0/D1)PE1_47") (pintype "bidirectional"))
    )
    (net (code "117") (name "TX1") (class "Default")
      (node (ref "MCU") (pin "28") (pinfunction "(INT3/TXD1/D21)PD3_28") (pintype "bidirectional"))
    )
    (net (code "118") (name "VBATT") (class "Default")
      (node (ref "C118") (pin "1") (pinfunction "1_1") (pintype "passive"))
      (node (ref "C119") (pin "1") (pinfunction "1_1") (pintype "passive"))
      (node (ref "C120") (pin "1") (pinfunction "1_1") (pintype "passive"))
      (node (ref "C126") (pin "1") (pinfunction "1_1") (pintype "passive"))
      (node (ref "C127") (pin "1") (pinfunction "1_1") (pintype "passive"))
      (node (ref "C2") (pin "1") (pinfunction "1_1") (pintype "passive"))
      (node (ref "C37") (pin "1") (pinfunction "1_1") (pintype "passive"))
      (node (ref "C38") (pin "1") (pinfunction "1_1") (pintype "passive"))
      (node (ref "C44") (pin "1") (pinfunction "1_1") (pintype "passive"))
      (node (ref "C45") (pin "1") (pinfunction "1_1") (pintype "passive"))
      (node (ref "C46") (pin "1") (pinfunction "1_1") (pintype "passive"))
      (node (ref "D13") (pin "K") (pinfunction "K_K") (pintype "passive"))
      (node (ref "D14") (pin "K") (pinfunction "K_K") (pintype "passive"))
      (node (ref "D8") (pin "K") (pinfunction "K_K") (pintype "passive"))
      (node (ref "LED3") (pin "A") (pinfunction "A_A") (pintype "passive"))
      (node (ref "SW1") (pin "S1") (pinfunction "2_S1") (pintype "passive"))
      (node (ref "VREG1") (pin "3") (pinfunction "VIN_3") (pintype "bidirectional"))
      (node (ref "VREG1") (pin "4") (pinfunction "VIN_4") (pintype "bidirectional"))
      (node (ref "VREG6") (pin "1") (pinfunction "VI_1") (pintype "bidirectional"))
      (node (ref "VREG7") (pin "1") (pinfunction "~{SHDN}_1") (pintype "bidirectional"))
      (node (ref "VREG7") (pin "2") (pinfunction "VIN_2") (pintype "bidirectional"))
    )
    (net (code "119") (name "VCC") (class "Default")
      (node (ref "AVR_ISP") (pin "2") (pinfunction "2_2") (pintype "passive"))
      (node (ref "C106") (pin "1") (pinfunction "1_1") (pintype "passive"))
      (node (ref "C107") (pin "1") (pinfunction "1_1") (pintype "passive"))
      (node (ref "C108") (pin "1") (pinfunction "1_1") (pintype "passive"))
      (node (ref "C109") (pin "1") (pinfunction "1_1") (pintype "passive"))
      (node (ref "C111") (pin "1") (pinfunction "1_1") (pintype "passive"))
      (node (ref "C116") (pin "1") (pinfunction "1_1") (pintype "passive"))
      (node (ref "C12") (pin "1") (pinfunction "1_1") (pintype "passive"))
      (node (ref "C123") (pin "1") (pinfunction "1_1") (pintype "passive"))
      (node (ref "C124") (pin "1") (pinfunction "1_1") (pintype "passive"))
      (node (ref "C16") (pin "1") (pinfunction "1_1") (pintype "passive"))
      (node (ref "C20") (pin "1") (pinfunction "1_1") (pintype "passive"))
      (node (ref "C25") (pin "1") (pinfunction "1_1") (pintype "passive"))
      (node (ref "C8") (pin "1") (pinfunction "1_1") (pintype "passive"))
      (node (ref "C98") (pin "1") (pinfunction "1_1") (pintype "passive"))
      (node (ref "C99") (pin "1") (pinfunction "1_1") (pintype "passive"))
      (node (ref "D11") (pin "K") (pinfunction "K_K") (pintype "passive"))
      (node (ref "D8") (pin "A") (pinfunction "A_A") (pintype "passive"))
      (node (ref "HBRIDGE1") (pin "7") (pinfunction "NSLEEP_7") (pintype "passive"))
      (node (ref "HBRIDGE1") (pin "8") (pinfunction "VCC_8") (pintype "passive"))
      (node (ref "HBRIDGE2") (pin "7") (pinfunction "NSLEEP_7") (pintype "passive"))
      (node (ref "HBRIDGE2") (pin "8") (pinfunction "VCC_8") (pintype "passive"))
      (node (ref "HBRIDGE3") (pin "7") (pinfunction "NSLEEP_7") (pintype "passive"))
      (node (ref "HBRIDGE3") (pin "8") (pinfunction "VCC_8") (pintype "passive"))
      (node (ref "HBRIDGE4") (pin "7") (pinfunction "NSLEEP_7") (pintype "passive"))
      (node (ref "HBRIDGE4") (pin "8") (pinfunction "VCC_8") (pintype "passive"))
      (node (ref "HBRIDGE5") (pin "7") (pinfunction "NSLEEP_7") (pintype "passive"))
      (node (ref "HBRIDGE5") (pin "8") (pinfunction "VCC_8") (pintype "passive"))
      (node (ref "JP2") (pin "VCC") (pinfunction "1_VCC") (pintype "passive"))
      (node (ref "L3") (pin "1") (pinfunction "1_1") (pintype "passive"))
      (node (ref "MCU") (pin "23") (pinfunction "DEVDD_23") (pintype "bidirectional"))
      (node (ref "MCU") (pin "34") (pinfunction "DEVDD_34") (pintype "bidirectional"))
      (node (ref "MCU") (pin "44") (pinfunction "DEVDD_44") (pintype "bidirectional"))
      (node (ref "MCU") (pin "54") (pinfunction "DEVDD_54") (pintype "bidirectional"))
      (node (ref "PWM_DRIVER1") (pin "28") (pinfunction "VCC_28") (pintype "passive"))
      (node (ref "R40") (pin "2") (pinfunction "2_2") (pintype "passive"))
      (node (ref "R41") (pin "2") (pinfunction "2_2") (pintype "passive"))
      (node (ref "R46") (pin "2") (pinfunction "2_2") (pintype "passive"))
      (node (ref "VREG1") (pin "5") (pinfunction "VOUT_5") (pintype "bidirectional"))
      (node (ref "VREG1") (pin "6") (pinfunction "VOUT_6") (pintype "bidirectional"))
    )
    (net (code "120") (name "VIBE_1") (class "Default")
      (node (ref "PWM_DRIVER1") (pin "6") (pinfunction "PWM0_6") (pintype "passive"))
      (node (ref "R6") (pin "1") (pinfunction "1_1") (pintype "passive"))
    )
    (net (code "121") (name "VIBE_2") (class "Default")
      (node (ref "PWM_DRIVER1") (pin "7") (pinfunction "PWM1_7") (pintype "passive"))
      (node (ref "R7") (pin "1") (pinfunction "1_1") (pintype "passive"))
    )
    (net (code "122") (name "VIBE_3") (class "Default")
      (node (ref "PWM_DRIVER1") (pin "8") (pinfunction "PWM2_8") (pintype "passive"))
      (node (ref "R8") (pin "1") (pinfunction "1_1") (pintype "passive"))
    )
    (net (code "123") (name "VIBE_4") (class "Default")
      (node (ref "PWM_DRIVER1") (pin "9") (pinfunction "PWM3_9") (pintype "passive"))
      (node (ref "R9") (pin "1") (pinfunction "1_1") (pintype "passive"))
    )
    (net (code "124") (name "VIBE_5") (class "Default")
      (node (ref "PWM_DRIVER1") (pin "10") (pinfunction "PWM4_10") (pintype "passive"))
      (node (ref "R10") (pin "1") (pinfunction "1_1") (pintype "passive"))
    )
    (net (code "125") (name "VIBE_6") (class "Default")
      (node (ref "PWM_DRIVER1") (pin "11") (pinfunction "PWM5_11") (pintype "passive"))
      (node (ref "R13") (pin "1") (pinfunction "1_1") (pintype "passive"))
    )
    (net (code "126") (name "unconnected-(JP2-5-PadCTS)") (class "Default")
      (node (ref "JP2") (pin "CTS") (pinfunction "5_CTS") (pintype "passive"))
    )
    (net (code "127") (name "unconnected-(MCU-RSTON-Pad13)") (class "Default")
      (node (ref "MCU") (pin "13") (pinfunction "RSTON_13") (pintype "bidirectional"))
    )
    (net (code "128") (name "unconnected-(SW1-3-PadS2)") (class "Default")
      (node (ref "SW1") (pin "S2") (pinfunction "3_S2") (pintype "passive"))
    )
    (net (code "129") (name "unconnected-(VREG1-FB{slash}NC-Pad7)") (class "Default")
      (node (ref "VREG1") (pin "7") (pinfunction "FB/NC_7") (pintype "bidirectional"))
    )
    (net (code "130") (name "unconnected-(VREG1-PG-Pad8)") (class "Default")
      (node (ref "VREG1") (pin "8") (pinfunction "PG_8") (pintype "bidirectional"))
    )
  )
)
